# Motherboard.net
KiCad netlist of a schematic drawn in EAGLE
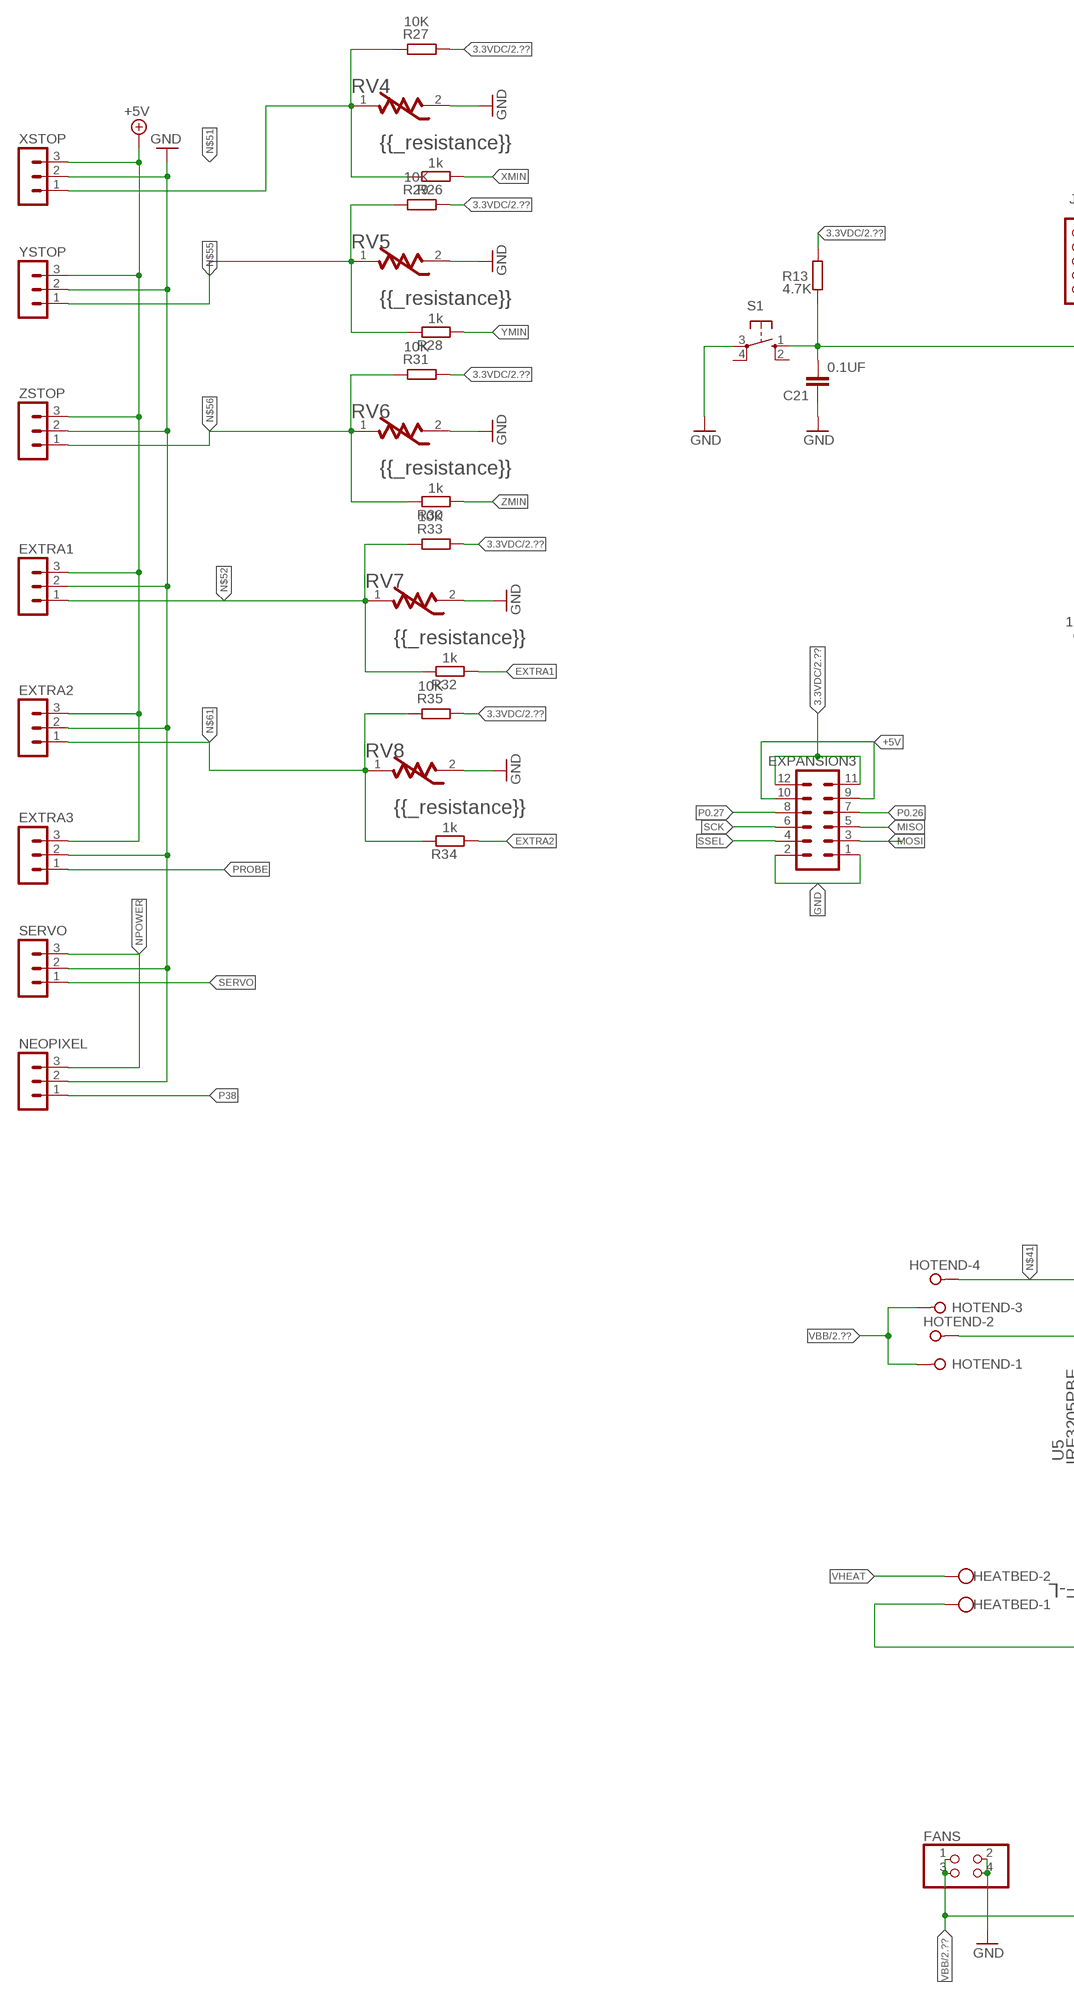
[diagram p0: schematic, sheet 1, part 1 of 2]
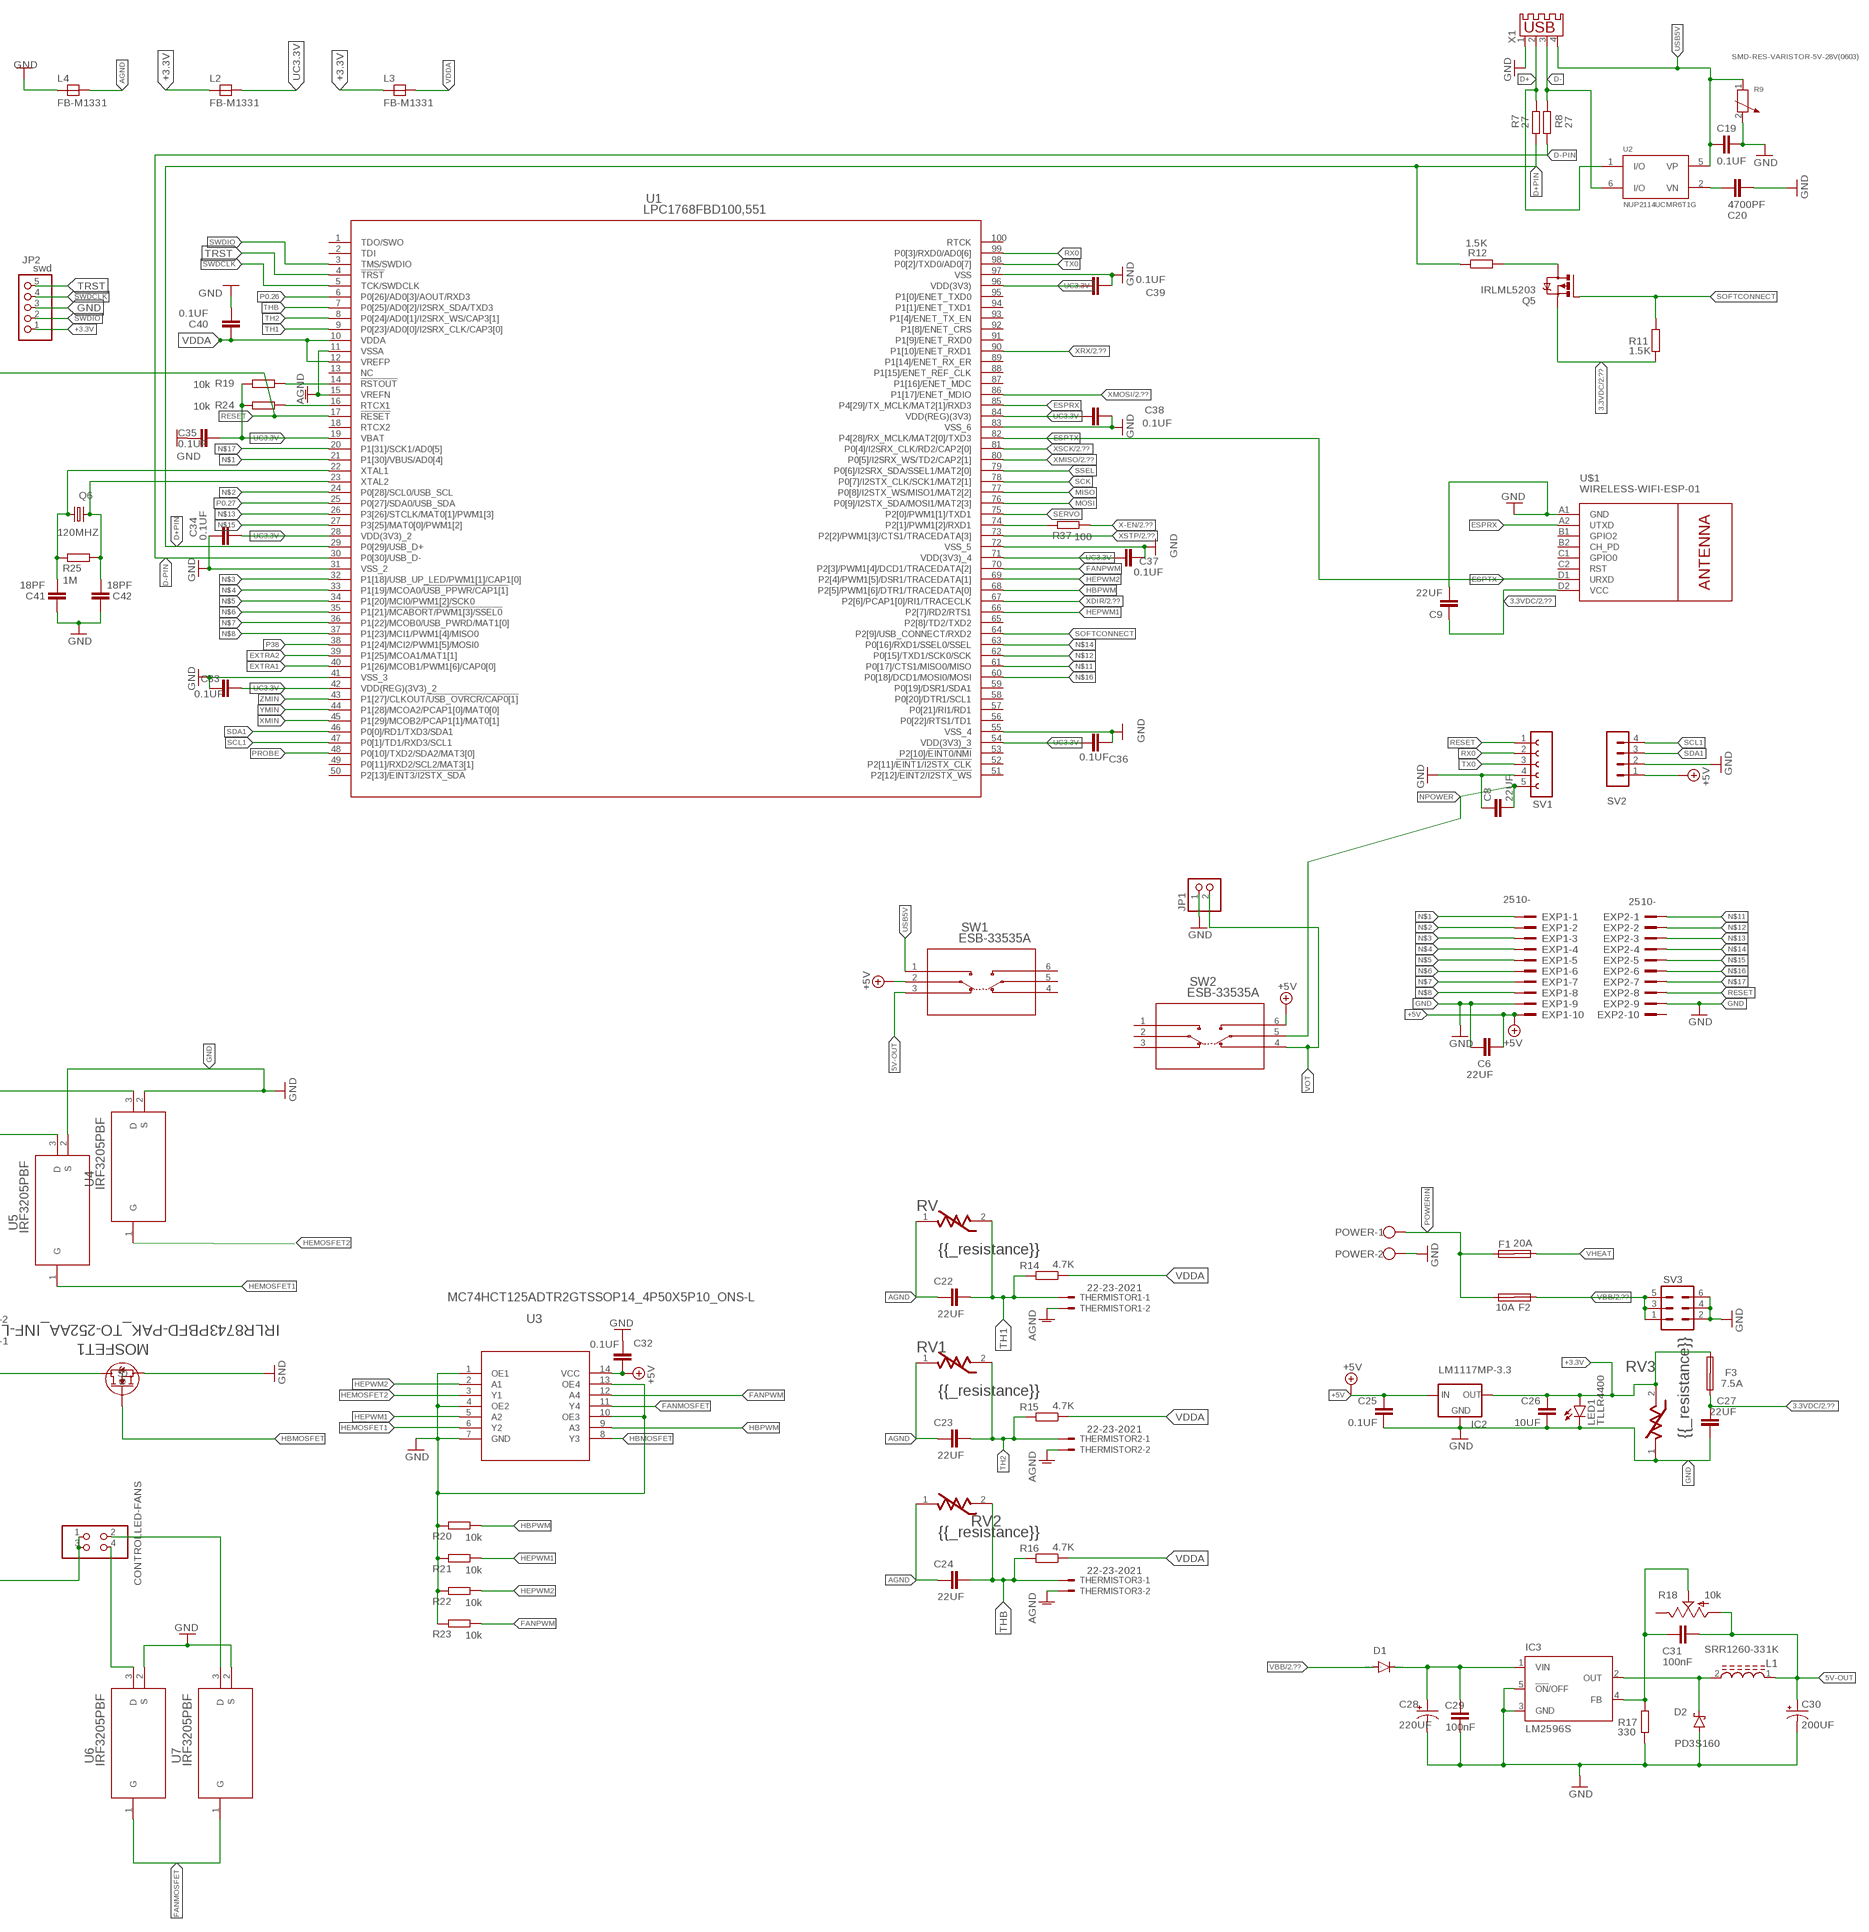
[diagram p1: schematic, sheet 1, part 2 of 2]
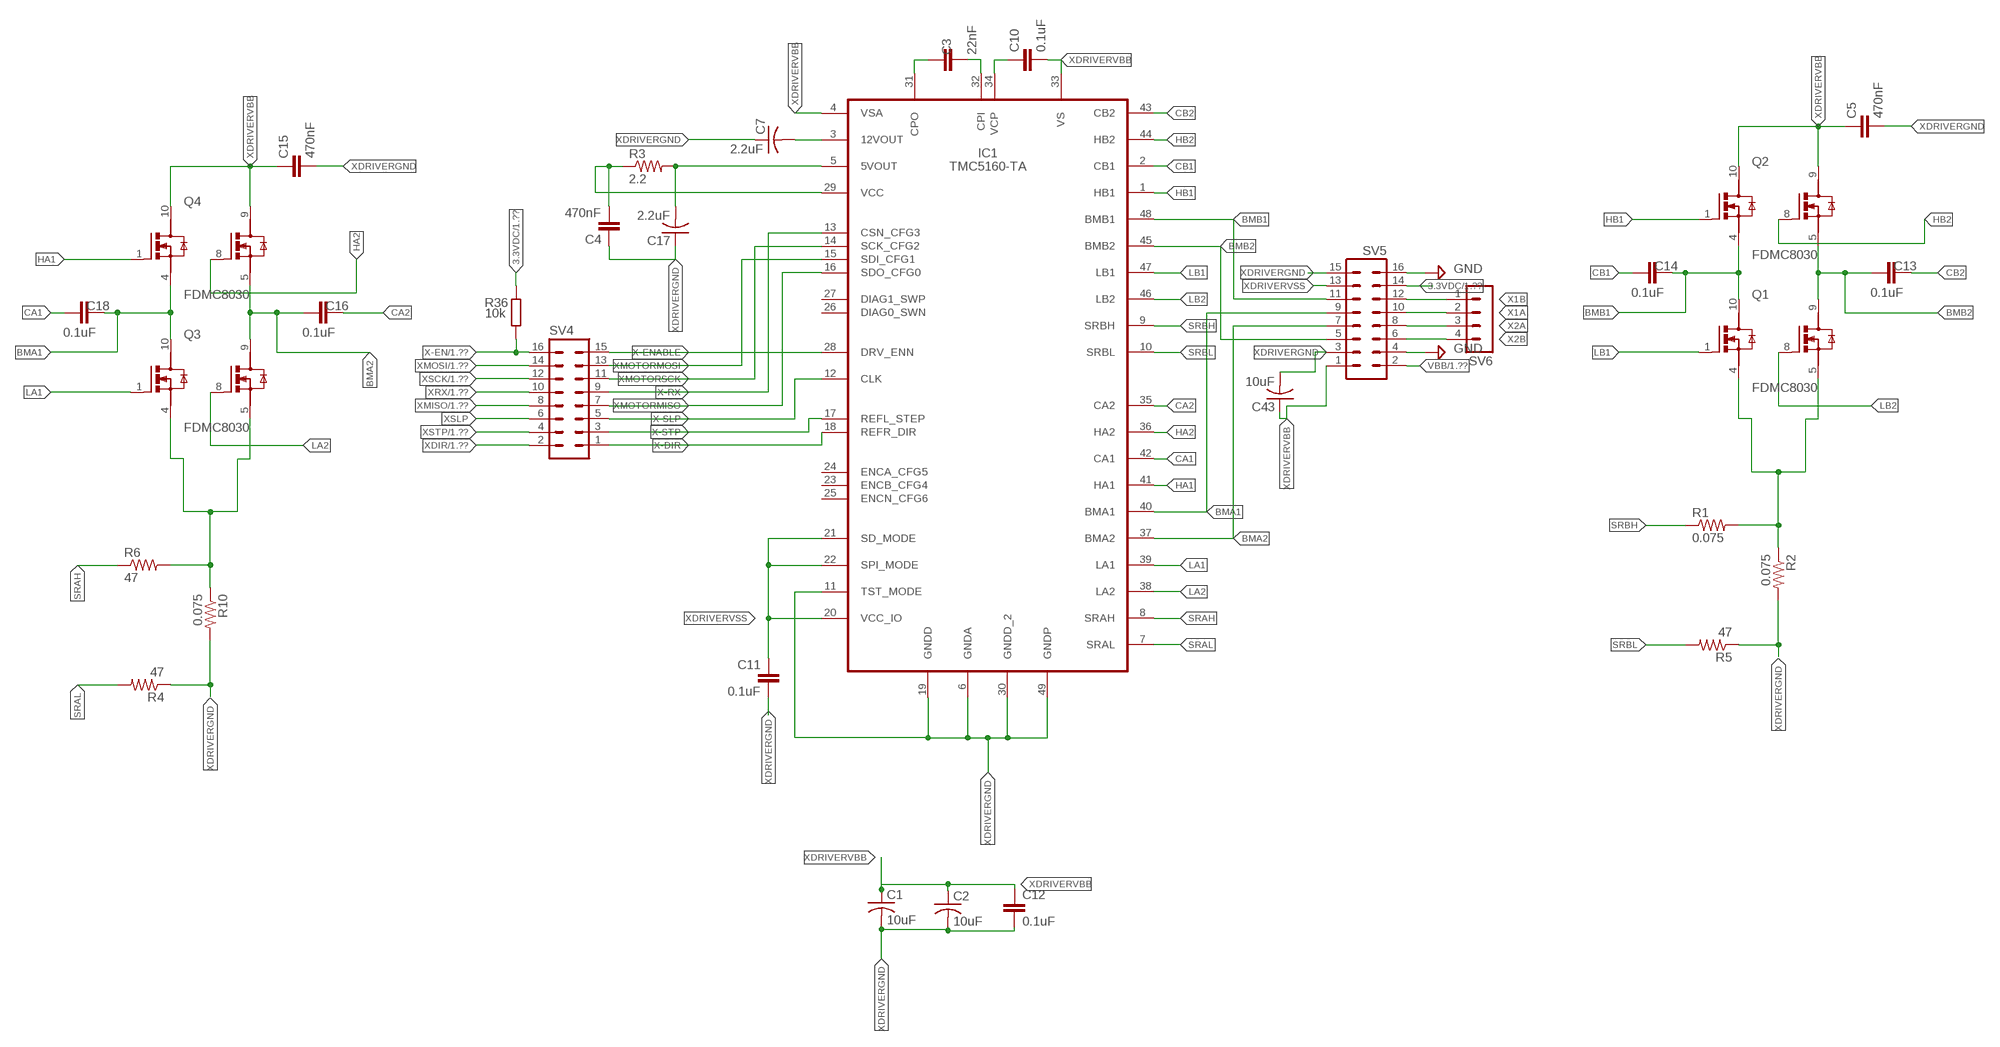
[diagram p2: schematic, sheet 2]

(export (version "E")
  (design (tool "Eeschema 10.0.6"))
  (components
    (comp (ref "C1")
      (value "10uF")
      (footprint "eagle-import:C0805")
      (libsource (lib "eagle-import") (part "C-USC0805"))
    )
    (comp (ref "C2")
      (value "10uF")
      (footprint "eagle-import:C0805")
      (libsource (lib "eagle-import") (part "C-USC0805"))
    )
    (comp (ref "C3")
      (value "22nF")
      (footprint "eagle-import:0603")
      (libsource (lib "eagle-import") (part "22NF/22,000PF-0603-50V-10%"))
    )
    (comp (ref "C4")
      (value "470nF")
      (footprint "eagle-import:0402")
      (libsource (lib "eagle-import") (part "470NF-0402-16V-10%"))
    )
    (comp (ref "C5")
      (value "470nF")
      (footprint "eagle-import:0402")
      (libsource (lib "eagle-import") (part "470NF-0402-16V-10%"))
    )
    (comp (ref "C7")
      (value "2.2uF")
      (footprint "eagle-import:C0402")
      (libsource (lib "eagle-import") (part "C-USC0402"))
    )
    (comp (ref "C10")
      (value "0.1uF")
      (footprint "eagle-import:0402")
      (libsource (lib "eagle-import") (part "0.1UF-0402-16V-10%"))
    )
    (comp (ref "C11")
      (value "0.1uF")
      (footprint "eagle-import:0402")
      (libsource (lib "eagle-import") (part "0.1UF-0402-16V-10%"))
    )
    (comp (ref "C12")
      (value "0.1uF")
      (footprint "eagle-import:0402")
      (libsource (lib "eagle-import") (part "0.1UF-0402-16V-10%"))
    )
    (comp (ref "C13")
      (value "0.1uF")
      (footprint "eagle-import:0402")
      (libsource (lib "eagle-import") (part "0.1UF-0402-16V-10%"))
    )
    (comp (ref "C14")
      (value "0.1uF")
      (footprint "eagle-import:0402")
      (libsource (lib "eagle-import") (part "0.1UF-0402-16V-10%"))
    )
    (comp (ref "C15")
      (value "470nF")
      (footprint "eagle-import:0402")
      (libsource (lib "eagle-import") (part "470NF-0402-16V-10%"))
    )
    (comp (ref "C16")
      (value "0.1uF")
      (footprint "eagle-import:0402")
      (libsource (lib "eagle-import") (part "0.1UF-0402-16V-10%"))
    )
    (comp (ref "C17")
      (value "2.2uF")
      (footprint "eagle-import:C0402")
      (libsource (lib "eagle-import") (part "C-USC0402"))
    )
    (comp (ref "C18")
      (value "0.1uF")
      (footprint "eagle-import:0402")
      (libsource (lib "eagle-import") (part "0.1UF-0402-16V-10%"))
    )
    (comp (ref "C43")
      (value "10uF")
      (footprint "eagle-import:C0805")
      (libsource (lib "eagle-import") (part "C-USC0805"))
    )
    (comp (ref "IC1")
      (value "TMC5160-TA")
      (footprint "eagle-import:TQFP48-EP")
      (fields (field (name "MF") "Trinamic Motion"))
      (libsource (lib "eagle-import") (part "TMC5160-TA"))
    )
    (comp (ref "Q1")
      (value "FDMC8030")
      (footprint "eagle-import:TRANS_FDMC8030")
      (fields (field (name "MF") "ON Semiconductor"))
      (libsource (lib "eagle-import") (part "FDMC8030"))
    )
    (comp (ref "Q2")
      (value "FDMC8030")
      (footprint "eagle-import:TRANS_FDMC8030")
      (fields (field (name "MF") "ON Semiconductor"))
      (libsource (lib "eagle-import") (part "FDMC8030"))
    )
    (comp (ref "Q3")
      (value "FDMC8030")
      (footprint "eagle-import:TRANS_FDMC8030")
      (fields (field (name "MF") "ON Semiconductor"))
      (libsource (lib "eagle-import") (part "FDMC8030"))
    )
    (comp (ref "Q4")
      (value "FDMC8030")
      (footprint "eagle-import:TRANS_FDMC8030")
      (fields (field (name "MF") "ON Semiconductor"))
      (libsource (lib "eagle-import") (part "FDMC8030"))
    )
    (comp (ref "R1")
      (value "0.075")
      (footprint "eagle-import:R1206")
      (libsource (lib "eagle-import") (part "R-US_R1206"))
    )
    (comp (ref "R2")
      (value "0.075")
      (footprint "eagle-import:R1206")
      (libsource (lib "eagle-import") (part "R-US_R1206"))
    )
    (comp (ref "R3")
      (value "2.2")
      (footprint "eagle-import:R0402")
      (libsource (lib "eagle-import") (part "R-US_R0402"))
    )
    (comp (ref "R4")
      (value "47")
      (footprint "eagle-import:R0402")
      (libsource (lib "eagle-import") (part "R-US_R0402"))
    )
    (comp (ref "R5")
      (value "47")
      (footprint "eagle-import:R0402")
      (libsource (lib "eagle-import") (part "R-US_R0402"))
    )
    (comp (ref "R6")
      (value "47")
      (footprint "eagle-import:R0402")
      (libsource (lib "eagle-import") (part "R-US_R0402"))
    )
    (comp (ref "R10")
      (value "0.075")
      (footprint "eagle-import:R1206")
      (libsource (lib "eagle-import") (part "R-US_R1206"))
    )
    (comp (ref "R36")
      (value "10k")
      (footprint "eagle-import:R0805")
      (libsource (lib "eagle-import") (part "R-EU_R0805"))
    )
    (comp (ref "SV4")
      (value "MA08-2")
      (footprint "eagle-import:MA08-2")
      (libsource (lib "eagle-import") (part "MA08-2"))
    )
    (comp (ref "SV5")
      (value "MA08-2")
      (footprint "eagle-import:MA08-2")
      (libsource (lib "eagle-import") (part "MA08-2"))
    )
    (comp (ref "SV6")
      (value "MA04-1")
      (footprint "eagle-import:MA04-1")
      (libsource (lib "eagle-import") (part "MA04-1"))
    )
    (comp (ref "C6")
      (value "22UF")
      (footprint "eagle-import:C0805")
      (libsource (lib "eagle-import") (part "C-EUC0805"))
    )
    (comp (ref "C8")
      (value "22UF")
      (footprint "eagle-import:C0805")
      (libsource (lib "eagle-import") (part "C-EUC0805"))
    )
    (comp (ref "C9")
      (value "22UF")
      (footprint "eagle-import:C0805")
      (libsource (lib "eagle-import") (part "C-EUC0805"))
    )
    (comp (ref "C19")
      (value "0.1UF")
      (footprint "eagle-import:C0805")
      (libsource (lib "eagle-import") (part "C-EUC0805"))
    )
    (comp (ref "C20")
      (value "4700PF")
      (footprint "eagle-import:C0805")
      (libsource (lib "eagle-import") (part "C-EUC0805"))
    )
    (comp (ref "C21")
      (value "0.1UF")
      (footprint "eagle-import:C0805")
      (libsource (lib "eagle-import") (part "C-EUC0805"))
    )
    (comp (ref "C22")
      (value "22UF")
      (footprint "eagle-import:C0805")
      (libsource (lib "eagle-import") (part "C-EUC0805"))
    )
    (comp (ref "C23")
      (value "22UF")
      (footprint "eagle-import:C0805")
      (libsource (lib "eagle-import") (part "C-EUC0805"))
    )
    (comp (ref "C24")
      (value "22UF")
      (footprint "eagle-import:C0805")
      (libsource (lib "eagle-import") (part "C-EUC0805"))
    )
    (comp (ref "C25")
      (value "0.1UF")
      (footprint "eagle-import:C0805")
      (libsource (lib "eagle-import") (part "C-EUC0805"))
    )
    (comp (ref "C26")
      (value "10UF")
      (footprint "eagle-import:C0805")
      (libsource (lib "eagle-import") (part "C-EUC0805"))
    )
    (comp (ref "C27")
      (value "22UF")
      (footprint "eagle-import:C0805")
      (libsource (lib "eagle-import") (part "C-EUC0805"))
    )
    (comp (ref "C28")
      (value "220UF")
      (footprint "eagle-import:E5-10,5")
      (libsource (lib "eagle-import") (part "CPOL-USE5-10.5"))
    )
    (comp (ref "C29")
      (value "100nF")
      (footprint "eagle-import:C0805")
      (libsource (lib "eagle-import") (part "C-EUC0805"))
    )
    (comp (ref "C30")
      (value "200UF")
      (footprint "eagle-import:E5-10,5")
      (libsource (lib "eagle-import") (part "CPOL-USE5-10.5"))
    )
    (comp (ref "C31")
      (value "100nF")
      (footprint "eagle-import:C0805")
      (libsource (lib "eagle-import") (part "C-EUC0805"))
    )
    (comp (ref "C32")
      (value "0.1UF")
      (footprint "eagle-import:C0805")
      (libsource (lib "eagle-import") (part "C-EUC0805"))
    )
    (comp (ref "C33")
      (value "0.1UF")
      (footprint "eagle-import:C0805")
      (libsource (lib "eagle-import") (part "C-EUC0805"))
    )
    (comp (ref "C34")
      (value "0.1UF")
      (footprint "eagle-import:C0805")
      (libsource (lib "eagle-import") (part "C-EUC0805"))
    )
    (comp (ref "C35")
      (value "0.1UF")
      (footprint "eagle-import:C0805")
      (libsource (lib "eagle-import") (part "C-EUC0805"))
    )
    (comp (ref "C36")
      (value "0.1UF")
      (footprint "eagle-import:C0805")
      (libsource (lib "eagle-import") (part "C-EUC0805"))
    )
    (comp (ref "C37")
      (value "0.1UF")
      (footprint "eagle-import:C0805")
      (libsource (lib "eagle-import") (part "C-EUC0805"))
    )
    (comp (ref "C38")
      (value "0.1UF")
      (footprint "eagle-import:C0805")
      (libsource (lib "eagle-import") (part "C-EUC0805"))
    )
    (comp (ref "C39")
      (value "0.1UF")
      (footprint "eagle-import:C0805")
      (libsource (lib "eagle-import") (part "C-EUC0805"))
    )
    (comp (ref "C40")
      (value "0.1UF")
      (footprint "eagle-import:C0805")
      (libsource (lib "eagle-import") (part "C-EUC0805"))
    )
    (comp (ref "C41")
      (value "18PF")
      (footprint "eagle-import:C0805")
      (libsource (lib "eagle-import") (part "C-EUC0805"))
    )
    (comp (ref "C42")
      (value "18PF")
      (footprint "eagle-import:C0805")
      (libsource (lib "eagle-import") (part "C-EUC0805"))
    )
    (comp (ref "CONTROLLED-FANS")
      (value "PINHD-2X2")
      (footprint "eagle-import:2X02")
      (libsource (lib "eagle-import") (part "PINHD-2X2"))
    )
    (comp (ref "D1")
      (value "DIODE-DO214AA")
      (footprint "eagle-import:DO214AA")
      (libsource (lib "eagle-import") (part "DIODE-DO214AA"))
    )
    (comp (ref "D2")
      (value "PD3S160")
      (footprint "eagle-import:POWERDI323")
      (libsource (lib "eagle-import") (part "PD3S160"))
    )
    (comp (ref "EXP1")
      (value "2510-")
      (footprint "eagle-import:PAK100_2500-10")
      (fields (field (name "MF") "3M") (field (name "MPN") "2510-6002UB"))
      (libsource (lib "eagle-import") (part "2510-"))
    )
    (comp (ref "EXP2")
      (value "2510-")
      (footprint "eagle-import:PAK100_2500-10")
      (fields (field (name "MF") "3M") (field (name "MPN") "2510-6002UB"))
      (libsource (lib "eagle-import") (part "2510-"))
    )
    (comp (ref "EXPANSION3")
      (value "MA06-2")
      (footprint "eagle-import:MA06-2")
      (libsource (lib "eagle-import") (part "MA06-2"))
    )
    (comp (ref "EXTRA1")
      (value "MA03-1")
      (footprint "eagle-import:MA03-1")
      (libsource (lib "eagle-import") (part "MA03-1"))
    )
    (comp (ref "EXTRA2")
      (value "MA03-1")
      (footprint "eagle-import:MA03-1")
      (libsource (lib "eagle-import") (part "MA03-1"))
    )
    (comp (ref "EXTRA3")
      (value "MA03-1")
      (footprint "eagle-import:MA03-1")
      (libsource (lib "eagle-import") (part "MA03-1"))
    )
    (comp (ref "F1")
      (value "20A")
      (footprint "eagle-import:SHK20Q")
      (libsource (lib "eagle-import") (part "SHK20Q"))
    )
    (comp (ref "F2")
      (value "10A")
      (footprint "eagle-import:SHK20Q")
      (libsource (lib "eagle-import") (part "SHK20Q"))
    )
    (comp (ref "F3")
      (value "7.5A")
      (footprint "eagle-import:SHK20Q")
      (libsource (lib "eagle-import") (part "SHK20Q"))
    )
    (comp (ref "FANS")
      (value "PINHD-2X2")
      (footprint "eagle-import:2X02")
      (libsource (lib "eagle-import") (part "PINHD-2X2"))
    )
    (comp (ref "HEATBED")
      (value "W237-102")
      (footprint "eagle-import:W237-102")
      (fields (field (name "MPN") "237-102"))
      (libsource (lib "eagle-import") (part "W237-102"))
    )
    (comp (ref "HOTEND")
      (value "W237-04P")
      (footprint "eagle-import:W237-4P")
      (libsource (lib "eagle-import") (part "W237-04P"))
    )
    (comp (ref "IC2")
      (value "LM1117MP-3.3")
      (footprint "eagle-import:SOT223")
      (fields (field (name "MF") "Texas Instruments"))
      (libsource (lib "eagle-import") (part "LM1117?-MP3.3"))
    )
    (comp (ref "IC3")
      (value "LM2596S")
      (footprint "eagle-import:TO263-5")
      (fields (field (name "MF") "NATIONAL SEMICONDUCTOR") (field (name "MPN") "LM2596S-ADJ/NOPB"))
      (libsource (lib "eagle-import") (part "LM2596S"))
    )
    (comp (ref "JP1")
      (value "PINHD-1X2")
      (footprint "eagle-import:1X02")
      (libsource (lib "eagle-import") (part "PINHD-1X2"))
    )
    (comp (ref "JP2")
      (value "swd")
      (footprint "eagle-import:1X05")
      (libsource (lib "eagle-import") (part "PINHD-1X5"))
    )
    (comp (ref "L1")
      (value "SRR1260-331K")
      (footprint "eagle-import:INDP125125X600N")
      (fields (field (name "MF") "Bourns"))
      (libsource (lib "eagle-import") (part "SRR1260-331K"))
    )
    (comp (ref "L2")
      (value "FB-M1331")
      (footprint "eagle-import:M1331")
      (libsource (lib "eagle-import") (part "FB-M1331"))
    )
    (comp (ref "L3")
      (value "FB-M1331")
      (footprint "eagle-import:M1331")
      (libsource (lib "eagle-import") (part "FB-M1331"))
    )
    (comp (ref "L4")
      (value "FB-M1331")
      (footprint "eagle-import:M1331")
      (libsource (lib "eagle-import") (part "FB-M1331"))
    )
    (comp (ref "LED1")
      (value "TLLR4400")
      (footprint "eagle-import:LED3MM")
      (fields (field (name "MF") "VISHAY SEMICONDUCTOR"))
      (libsource (lib "eagle-import") (part "TLLR4400"))
    )
    (comp (ref "MOSFET1")
      (value "IRLR8743PBFD-PAK_TO-252AA_INF-L")
      (footprint "eagle-import:D-PAK_TO-252AA_INF-L")
      (fields
        (field (name "MANUFACTURER_PART_NUMBER") "IRLR8743PBF")
        (field (name "COPYRIGHT") "Copyright (C) 2018 Accelerated Designs. All rights reserved")
      )
      (libsource (lib "eagle-import") (part "IRLR8743PBFD-PAK_TO-252AA_INF-L"))
    )
    (comp (ref "NEOPIXEL")
      (value "MA03-1")
      (footprint "eagle-import:MA03-1")
      (libsource (lib "eagle-import") (part "MA03-1"))
    )
    (comp (ref "POWER")
      (value "W237-102")
      (footprint "eagle-import:W237-102")
      (fields (field (name "MPN") "237-102"))
      (libsource (lib "eagle-import") (part "W237-102"))
    )
    (comp (ref "Q5")
      (value "IRLML5203")
      (footprint "eagle-import:MICRO3")
      (libsource (lib "eagle-import") (part "IRLML5203"))
    )
    (comp (ref "Q6")
      (value "120MHZ")
      (footprint "eagle-import:HC49_S")
      (libsource (lib "eagle-import") (part "CRYSTALHC49S"))
    )
    (comp (ref "R7")
      (value "27")
      (footprint "eagle-import:R0805")
      (libsource (lib "eagle-import") (part "R-EU_R0805"))
    )
    (comp (ref "R8")
      (value "27")
      (footprint "eagle-import:R0805")
      (libsource (lib "eagle-import") (part "R-EU_R0805"))
    )
    (comp (ref "R9")
      (value "SMD-RES-VARISTOR-5V-28V(0603)")
      (footprint "eagle-import:R0603")
      (fields
        (field (name "DIGI-KEY_PART_NUMBER") "CG0603MLC-05ECT-ND")
        (field (name "MF") "Bourns")
        (field (name "MP") "CG0603MLC-05E")
      )
      (libsource (lib "eagle-import") (part "SMD-RES-VARISTOR-5V-28V(0603)"))
    )
    (comp (ref "R11")
      (value "1.5K")
      (footprint "eagle-import:R0805")
      (libsource (lib "eagle-import") (part "R-EU_R0805"))
    )
    (comp (ref "R12")
      (value "1.5K")
      (footprint "eagle-import:R0805")
      (libsource (lib "eagle-import") (part "R-EU_R0805"))
    )
    (comp (ref "R13")
      (value "4.7K")
      (footprint "eagle-import:R0805")
      (libsource (lib "eagle-import") (part "R-EU_R0805"))
    )
    (comp (ref "R14")
      (value "4.7K")
      (footprint "eagle-import:R0805")
      (libsource (lib "eagle-import") (part "R-EU_R0805"))
    )
    (comp (ref "R15")
      (value "4.7K")
      (footprint "eagle-import:R0805")
      (libsource (lib "eagle-import") (part "R-EU_R0805"))
    )
    (comp (ref "R16")
      (value "4.7K")
      (footprint "eagle-import:R0805")
      (libsource (lib "eagle-import") (part "R-EU_R0805"))
    )
    (comp (ref "R17")
      (value "330")
      (footprint "eagle-import:R0805")
      (libsource (lib "eagle-import") (part "R-EU_R0805"))
    )
    (comp (ref "R18")
      (value "10k")
      (footprint "eagle-import:B64Y")
      (libsource (lib "eagle-import") (part "TRIM_US-B64Y"))
    )
    (comp (ref "R19")
      (value "10k")
      (footprint "eagle-import:R0805")
      (libsource (lib "eagle-import") (part "R-EU_R0805"))
    )
    (comp (ref "R20")
      (value "10k")
      (footprint "eagle-import:R0805")
      (libsource (lib "eagle-import") (part "R-EU_R0805"))
    )
    (comp (ref "R21")
      (value "10k")
      (footprint "eagle-import:R0805")
      (libsource (lib "eagle-import") (part "R-EU_R0805"))
    )
    (comp (ref "R22")
      (value "10k")
      (footprint "eagle-import:R0805")
      (libsource (lib "eagle-import") (part "R-EU_R0805"))
    )
    (comp (ref "R23")
      (value "10k")
      (footprint "eagle-import:R0805")
      (libsource (lib "eagle-import") (part "R-EU_R0805"))
    )
    (comp (ref "R24")
      (value "10k")
      (footprint "eagle-import:R0805")
      (libsource (lib "eagle-import") (part "R-EU_R0805"))
    )
    (comp (ref "R25")
      (value "1M")
      (footprint "eagle-import:R0805")
      (libsource (lib "eagle-import") (part "R-EU_R0805"))
    )
    (comp (ref "R26")
      (value "1k")
      (footprint "eagle-import:R0805")
      (libsource (lib "eagle-import") (part "R-EU_R0805"))
    )
    (comp (ref "R27")
      (value "10K")
      (footprint "eagle-import:R0805")
      (libsource (lib "eagle-import") (part "R-EU_R0805"))
    )
    (comp (ref "R28")
      (value "1k")
      (footprint "eagle-import:R0805")
      (libsource (lib "eagle-import") (part "R-EU_R0805"))
    )
    (comp (ref "R29")
      (value "10K")
      (footprint "eagle-import:R0805")
      (libsource (lib "eagle-import") (part "R-EU_R0805"))
    )
    (comp (ref "R30")
      (value "1k")
      (footprint "eagle-import:R0805")
      (libsource (lib "eagle-import") (part "R-EU_R0805"))
    )
    (comp (ref "R31")
      (value "10K")
      (footprint "eagle-import:R0805")
      (libsource (lib "eagle-import") (part "R-EU_R0805"))
    )
    (comp (ref "R32")
      (value "1k")
      (footprint "eagle-import:R0805")
      (libsource (lib "eagle-import") (part "R-EU_R0805"))
    )
    (comp (ref "R33")
      (value "10K")
      (footprint "eagle-import:R0805")
      (libsource (lib "eagle-import") (part "R-EU_R0805"))
    )
    (comp (ref "R34")
      (value "1k")
      (footprint "eagle-import:R0805")
      (libsource (lib "eagle-import") (part "R-EU_R0805"))
    )
    (comp (ref "R35")
      (value "10K")
      (footprint "eagle-import:R0805")
      (libsource (lib "eagle-import") (part "R-EU_R0805"))
    )
    (comp (ref "R37")
      (value "100")
      (footprint "eagle-import:R0805")
      (libsource (lib "eagle-import") (part "R-EU_R0805"))
    )
    (comp (ref "RV")
      (value "BOURNS_INC._CG0603MLC-3.3LEBOURNS_INC._CG0603MLC-3.3LE_0_1")
      (footprint "eagle-import:BOURNS_INC._CG0603MLC-3.3LE_1")
      (fields
        (field (name "DIGIKEY_PART_NUMBER") "CG0603MLC-3.3LECT-ND")
        (field (name "MF") "Bourns Inc.")
        (field (name "MOUSER_PART_NUMBER") "652-CG0603MLC-3.3LE")
      )
      (libsource (lib "eagle-import") (part "BOURNS_INC._CG0603MLC-3.3LEBOURNS_INC._CG0603MLC-3.3LE_0_1"))
    )
    (comp (ref "RV1")
      (value "BOURNS_INC._CG0603MLC-3.3LEBOURNS_INC._CG0603MLC-3.3LE_0_1")
      (footprint "eagle-import:BOURNS_INC._CG0603MLC-3.3LE_1")
      (fields
        (field (name "DIGIKEY_PART_NUMBER") "CG0603MLC-3.3LECT-ND")
        (field (name "MF") "Bourns Inc.")
        (field (name "MOUSER_PART_NUMBER") "652-CG0603MLC-3.3LE")
      )
      (libsource (lib "eagle-import") (part "BOURNS_INC._CG0603MLC-3.3LEBOURNS_INC._CG0603MLC-3.3LE_0_1"))
    )
    (comp (ref "RV2")
      (value "BOURNS_INC._CG0603MLC-3.3LEBOURNS_INC._CG0603MLC-3.3LE_0_1")
      (footprint "eagle-import:BOURNS_INC._CG0603MLC-3.3LE_1")
      (fields
        (field (name "DIGIKEY_PART_NUMBER") "CG0603MLC-3.3LECT-ND")
        (field (name "MF") "Bourns Inc.")
        (field (name "MOUSER_PART_NUMBER") "652-CG0603MLC-3.3LE")
      )
      (libsource (lib "eagle-import") (part "BOURNS_INC._CG0603MLC-3.3LEBOURNS_INC._CG0603MLC-3.3LE_0_1"))
    )
    (comp (ref "RV3")
      (value "BOURNS_INC._CG0603MLC-3.3LEBOURNS_INC._CG0603MLC-3.3LE_0_1")
      (footprint "eagle-import:BOURNS_INC._CG0603MLC-3.3LE_1")
      (fields
        (field (name "DIGIKEY_PART_NUMBER") "CG0603MLC-3.3LECT-ND")
        (field (name "MF") "Bourns Inc.")
        (field (name "MOUSER_PART_NUMBER") "652-CG0603MLC-3.3LE")
      )
      (libsource (lib "eagle-import") (part "BOURNS_INC._CG0603MLC-3.3LEBOURNS_INC._CG0603MLC-3.3LE_0_1"))
    )
    (comp (ref "RV4")
      (value "BOURNS_INC._CG0603MLC-3.3LEBOURNS_INC._CG0603MLC-3.3LE_0_1")
      (footprint "eagle-import:BOURNS_INC._CG0603MLC-3.3LE_1")
      (fields
        (field (name "DIGIKEY_PART_NUMBER") "CG0603MLC-3.3LECT-ND")
        (field (name "MF") "Bourns Inc.")
        (field (name "MOUSER_PART_NUMBER") "652-CG0603MLC-3.3LE")
      )
      (libsource (lib "eagle-import") (part "BOURNS_INC._CG0603MLC-3.3LEBOURNS_INC._CG0603MLC-3.3LE_0_1"))
    )
    (comp (ref "RV5")
      (value "BOURNS_INC._CG0603MLC-3.3LEBOURNS_INC._CG0603MLC-3.3LE_0_1")
      (footprint "eagle-import:BOURNS_INC._CG0603MLC-3.3LE_1")
      (fields
        (field (name "DIGIKEY_PART_NUMBER") "CG0603MLC-3.3LECT-ND")
        (field (name "MF") "Bourns Inc.")
        (field (name "MOUSER_PART_NUMBER") "652-CG0603MLC-3.3LE")
      )
      (libsource (lib "eagle-import") (part "BOURNS_INC._CG0603MLC-3.3LEBOURNS_INC._CG0603MLC-3.3LE_0_1"))
    )
    (comp (ref "RV6")
      (value "BOURNS_INC._CG0603MLC-3.3LEBOURNS_INC._CG0603MLC-3.3LE_0_1")
      (footprint "eagle-import:BOURNS_INC._CG0603MLC-3.3LE_1")
      (fields
        (field (name "DIGIKEY_PART_NUMBER") "CG0603MLC-3.3LECT-ND")
        (field (name "MF") "Bourns Inc.")
        (field (name "MOUSER_PART_NUMBER") "652-CG0603MLC-3.3LE")
      )
      (libsource (lib "eagle-import") (part "BOURNS_INC._CG0603MLC-3.3LEBOURNS_INC._CG0603MLC-3.3LE_0_1"))
    )
    (comp (ref "RV7")
      (value "BOURNS_INC._CG0603MLC-3.3LEBOURNS_INC._CG0603MLC-3.3LE_0_1")
      (footprint "eagle-import:BOURNS_INC._CG0603MLC-3.3LE_1")
      (fields
        (field (name "DIGIKEY_PART_NUMBER") "CG0603MLC-3.3LECT-ND")
        (field (name "MF") "Bourns Inc.")
        (field (name "MOUSER_PART_NUMBER") "652-CG0603MLC-3.3LE")
      )
      (libsource (lib "eagle-import") (part "BOURNS_INC._CG0603MLC-3.3LEBOURNS_INC._CG0603MLC-3.3LE_0_1"))
    )
    (comp (ref "RV8")
      (value "BOURNS_INC._CG0603MLC-3.3LEBOURNS_INC._CG0603MLC-3.3LE_0_1")
      (footprint "eagle-import:BOURNS_INC._CG0603MLC-3.3LE_1")
      (fields
        (field (name "DIGIKEY_PART_NUMBER") "CG0603MLC-3.3LECT-ND")
        (field (name "MF") "Bourns Inc.")
        (field (name "MOUSER_PART_NUMBER") "652-CG0603MLC-3.3LE")
      )
      (libsource (lib "eagle-import") (part "BOURNS_INC._CG0603MLC-3.3LEBOURNS_INC._CG0603MLC-3.3LE_0_1"))
    )
    (comp (ref "S1")
      (value "10-XX")
      (footprint "eagle-import:B3F-10XX")
      (fields (field (name "MPN") "B3F-1000"))
      (libsource (lib "eagle-import") (part "10-XX"))
    )
    (comp (ref "SERVO")
      (value "MA03-1")
      (footprint "eagle-import:MA03-1")
      (libsource (lib "eagle-import") (part "MA03-1"))
    )
    (comp (ref "SV1")
      (value "FE05-1")
      (footprint "eagle-import:FE05-1")
      (libsource (lib "eagle-import") (part "FE05-1"))
    )
    (comp (ref "SV2")
      (value "MA04-1")
      (footprint "eagle-import:MA04-1")
      (libsource (lib "eagle-import") (part "MA04-1"))
    )
    (comp (ref "SV3")
      (value "MA03-2")
      (footprint "eagle-import:MA03-2")
      (libsource (lib "eagle-import") (part "MA03-2"))
    )
    (comp (ref "SW1")
      (value "ESB-33535A")
      (footprint "eagle-import:ESB335_PAN")
      (fields (field (name "COPYRIGHT") "Copyright (C) 2018 Accelerated Designs. All rights reserved"))
      (libsource (lib "eagle-import") (part "ESB-33535A"))
    )
    (comp (ref "SW2")
      (value "ESB-33535A")
      (footprint "eagle-import:ESB335_PAN")
      (fields (field (name "COPYRIGHT") "Copyright (C) 2018 Accelerated Designs. All rights reserved"))
      (libsource (lib "eagle-import") (part "ESB-33535A"))
    )
    (comp (ref "THERMISTOR1")
      (value "22-23-2021")
      (footprint "eagle-import:22-23-2021")
      (fields (field (name "MF") "MOLEX"))
      (libsource (lib "eagle-import") (part "22-23-2021"))
    )
    (comp (ref "THERMISTOR2")
      (value "22-23-2021")
      (footprint "eagle-import:22-23-2021")
      (fields (field (name "MF") "MOLEX"))
      (libsource (lib "eagle-import") (part "22-23-2021"))
    )
    (comp (ref "THERMISTOR3")
      (value "22-23-2021")
      (footprint "eagle-import:22-23-2021")
      (fields (field (name "MF") "MOLEX"))
      (libsource (lib "eagle-import") (part "22-23-2021"))
    )
    (comp (ref "U$1")
      (value "WIRELESS-WIFI-ESP-01")
      (footprint "eagle-import:WIRELESS-WIFI-ESP-01")
      (libsource (lib "eagle-import") (part "WIRELESS-WIFI-ESP-01"))
    )
    (comp (ref "U1")
      (value "LPC1768FBD100,551")
      (footprint "eagle-import:LQFP100_14X14_NXP")
      (fields (field (name "COPYRIGHT") "Copyright (C) 2016 Accelerated Designs. All rights reserved"))
      (libsource (lib "eagle-import") (part "LPC1768FBD100,551"))
    )
    (comp (ref "U2")
      (value "NUP2114UCMR6T1G")
      (footprint "eagle-import:SOP95P275X110-6N")
      (fields
        (field (name "DIGI-KEY_PART_NUMBER") "NUP2114UCMR6T1GOSCT-ND")
        (field (name "MF") "ON Semiconductor")
      )
      (libsource (lib "eagle-import") (part "NUP2114UCMR6T1G"))
    )
    (comp (ref "U3")
      (value "MC74HCT125ADTR2GTSSOP14_4P50X5P10_ONS-L")
      (footprint "eagle-import:TSSOP14_4P50X5P10_ONS-L")
      (fields
        (field (name "MANUFACTURER_PART_NUMBER") "MC74HCT125ADTR2G")
        (field (name "COPYRIGHT") "Copyright (C) 2016 Accelerated Designs. All rights reserved")
      )
      (libsource (lib "eagle-import") (part "MC74HCT125ADTR2GTSSOP14_4P50X5P10_ONS-L"))
    )
    (comp (ref "U4")
      (value "IRF3205PBF")
      (footprint "eagle-import:PG-TO220-3_INF")
      (fields (field (name "COPYRIGHT") "Copyright (C) 2018 Accelerated Designs. All rights reserved"))
      (libsource (lib "eagle-import") (part "IRF3205PBF"))
    )
    (comp (ref "U5")
      (value "IRF3205PBF")
      (footprint "eagle-import:PG-TO220-3_INF")
      (fields (field (name "COPYRIGHT") "Copyright (C) 2018 Accelerated Designs. All rights reserved"))
      (libsource (lib "eagle-import") (part "IRF3205PBF"))
    )
    (comp (ref "U6")
      (value "IRF3205PBF")
      (footprint "eagle-import:PG-TO220-3_INF")
      (fields (field (name "COPYRIGHT") "Copyright (C) 2018 Accelerated Designs. All rights reserved"))
      (libsource (lib "eagle-import") (part "IRF3205PBF"))
    )
    (comp (ref "U7")
      (value "IRF3205PBF")
      (footprint "eagle-import:PG-TO220-3_INF")
      (fields (field (name "COPYRIGHT") "Copyright (C) 2018 Accelerated Designs. All rights reserved"))
      (libsource (lib "eagle-import") (part "IRF3205PBF"))
    )
    (comp (ref "X1")
      (value "USB-A003")
      (footprint "eagle-import:USB-A003")
      (libsource (lib "eagle-import") (part "USB-A003"))
    )
    (comp (ref "XSTOP")
      (value "MA03-1")
      (footprint "eagle-import:MA03-1")
      (libsource (lib "eagle-import") (part "MA03-1"))
    )
    (comp (ref "YSTOP")
      (value "MA03-1")
      (footprint "eagle-import:MA03-1")
      (libsource (lib "eagle-import") (part "MA03-1"))
    )
    (comp (ref "ZSTOP")
      (value "MA03-1")
      (footprint "eagle-import:MA03-1")
      (libsource (lib "eagle-import") (part "MA03-1"))
    )
  )
  (nets
    (net (code "1") (name "+3.3V") (class "Default")
      (node (ref "C26") (pin "1") (pinfunction "1_1") (pintype "passive"))
      (node (ref "F3") (pin "2A") (pinfunction "2A_2A") (pintype "passive"))
      (node (ref "IC2") (pin "2") (pinfunction "OUT_2") (pintype "passive"))
      (node (ref "IC2") (pin "4") (pinfunction "OUT_4") (pintype "passive"))
      (node (ref "JP2") (pin "1") (pinfunction "1_1") (pintype "passive"))
      (node (ref "L2") (pin "1") (pinfunction "1_1") (pintype "passive"))
      (node (ref "L3") (pin "1") (pinfunction "1_1") (pintype "passive"))
      (node (ref "LED1") (pin "A") (pinfunction "A_A") (pintype "passive"))
      (node (ref "RV3") (pin "2") (pinfunction "2_2") (pintype "passive"))
    )
    (net (code "2") (name "+5V") (class "Default")
      (node (ref "C25") (pin "1") (pinfunction "1_1") (pintype "passive"))
      (node (ref "C32") (pin "2") (pinfunction "2_2") (pintype "passive"))
      (node (ref "C6") (pin "1") (pinfunction "1_1") (pintype "passive"))
      (node (ref "EXP1") (pin "10") (pinfunction "KL_10") (pintype "passive"))
      (node (ref "EXPANSION3") (pin "10") (pinfunction "10_10") (pintype "passive"))
      (node (ref "EXPANSION3") (pin "9") (pinfunction "9_9") (pintype "passive"))
      (node (ref "EXTRA1") (pin "3") (pinfunction "3_3") (pintype "passive"))
      (node (ref "EXTRA2") (pin "3") (pinfunction "3_3") (pintype "passive"))
      (node (ref "EXTRA3") (pin "3") (pinfunction "3_3") (pintype "passive"))
      (node (ref "IC2") (pin "3") (pinfunction "IN_3") (pintype "input"))
      (node (ref "SV2") (pin "1") (pinfunction "1_1") (pintype "passive"))
      (node (ref "SW1") (pin "2") (pinfunction "2_2") (pintype "passive"))
      (node (ref "SW2") (pin "6") (pinfunction "6_6") (pintype "passive"))
      (node (ref "U3") (pin "14") (pinfunction "VCC_14") (pintype "power_in"))
      (node (ref "XSTOP") (pin "3") (pinfunction "3_3") (pintype "passive"))
      (node (ref "YSTOP") (pin "3") (pinfunction "3_3") (pintype "passive"))
      (node (ref "ZSTOP") (pin "3") (pinfunction "3_3") (pintype "passive"))
    )
    (net (code "3") (name "3.3VDC") (class "Default")
      (node (ref "C27") (pin "1") (pinfunction "1_1") (pintype "passive"))
      (node (ref "C9") (pin "1") (pinfunction "1_1") (pintype "passive"))
      (node (ref "EXPANSION3") (pin "11") (pinfunction "11_11") (pintype "passive"))
      (node (ref "EXPANSION3") (pin "12") (pinfunction "12_12") (pintype "passive"))
      (node (ref "F3") (pin "1A") (pinfunction "1A_1A") (pintype "passive"))
      (node (ref "Q5") (pin "2") (pinfunction "S_2") (pintype "passive"))
      (node (ref "R11") (pin "2") (pinfunction "2_2") (pintype "passive"))
      (node (ref "R13") (pin "1") (pinfunction "1_1") (pintype "passive"))
      (node (ref "R27") (pin "2") (pinfunction "2_2") (pintype "passive"))
      (node (ref "R29") (pin "2") (pinfunction "2_2") (pintype "passive"))
      (node (ref "R31") (pin "2") (pinfunction "2_2") (pintype "passive"))
      (node (ref "R33") (pin "2") (pinfunction "2_2") (pintype "passive"))
      (node (ref "R35") (pin "2") (pinfunction "2_2") (pintype "passive"))
      (node (ref "R36") (pin "1") (pinfunction "1_1") (pintype "passive"))
      (node (ref "SV5") (pin "14") (pinfunction "14_14") (pintype "passive"))
      (node (ref "U$1") (pin "D2") (pinfunction "VCC_D2") (pintype "power_in"))
    )
    (net (code "4") (name "5V-OUT") (class "Default")
      (node (ref "C30") (pin "+") (pinfunction "+_+") (pintype "passive"))
      (node (ref "C31") (pin "2") (pinfunction "2_2") (pintype "passive"))
      (node (ref "L1") (pin "1") (pinfunction "1_1") (pintype "passive"))
      (node (ref "R18") (pin "A") (pinfunction "A_A") (pintype "passive"))
      (node (ref "SW1") (pin "3") (pinfunction "3_3") (pintype "passive"))
    )
    (net (code "5") (name "AGND") (class "Default")
      (node (ref "C22") (pin "1") (pinfunction "1_1") (pintype "passive"))
      (node (ref "C23") (pin "1") (pinfunction "1_1") (pintype "passive"))
      (node (ref "C24") (pin "1") (pinfunction "1_1") (pintype "passive"))
      (node (ref "L4") (pin "2") (pinfunction "2_2") (pintype "passive"))
      (node (ref "RV") (pin "1") (pinfunction "1_1") (pintype "passive"))
      (node (ref "RV1") (pin "1") (pinfunction "1_1") (pintype "passive"))
      (node (ref "RV2") (pin "1") (pinfunction "1_1") (pintype "passive"))
      (node (ref "THERMISTOR1") (pin "2") (pinfunction "S_2") (pintype "passive"))
      (node (ref "THERMISTOR2") (pin "2") (pinfunction "S_2") (pintype "passive"))
      (node (ref "THERMISTOR3") (pin "2") (pinfunction "S_2") (pintype "passive"))
      (node (ref "U1") (pin "11") (pinfunction "VSSA_11") (pintype "power_in"))
      (node (ref "U1") (pin "15") (pinfunction "VREFN_15") (pintype "input"))
    )
    (net (code "6") (name "BMA1") (class "Default")
      (node (ref "C18") (pin "2") (pinfunction "2_2") (pintype "passive"))
      (node (ref "IC1") (pin "40") (pinfunction "BMA1_40") (pintype "input"))
      (node (ref "Q3") (pin "10") (pinfunction "D1_10") (pintype "passive"))
      (node (ref "Q4") (pin "4") (pinfunction "S1_4") (pintype "passive"))
      (node (ref "SV5") (pin "9") (pinfunction "9_9") (pintype "passive"))
    )
    (net (code "7") (name "BMA2") (class "Default")
      (node (ref "C16") (pin "1") (pinfunction "1_1") (pintype "passive"))
      (node (ref "IC1") (pin "37") (pinfunction "BMA2_37") (pintype "input"))
      (node (ref "Q3") (pin "9") (pinfunction "D2_9") (pintype "passive"))
      (node (ref "Q4") (pin "5") (pinfunction "S2_5") (pintype "passive"))
      (node (ref "SV5") (pin "7") (pinfunction "7_7") (pintype "passive"))
    )
    (net (code "8") (name "BMB1") (class "Default")
      (node (ref "C14") (pin "2") (pinfunction "2_2") (pintype "passive"))
      (node (ref "IC1") (pin "48") (pinfunction "BMB1_48") (pintype "input"))
      (node (ref "Q1") (pin "10") (pinfunction "D1_10") (pintype "passive"))
      (node (ref "Q2") (pin "4") (pinfunction "S1_4") (pintype "passive"))
      (node (ref "SV5") (pin "11") (pinfunction "11_11") (pintype "passive"))
    )
    (net (code "9") (name "BMB2") (class "Default")
      (node (ref "C13") (pin "1") (pinfunction "1_1") (pintype "passive"))
      (node (ref "IC1") (pin "45") (pinfunction "BMB2_45") (pintype "input"))
      (node (ref "Q1") (pin "9") (pinfunction "D2_9") (pintype "passive"))
      (node (ref "Q2") (pin "5") (pinfunction "S2_5") (pintype "passive"))
      (node (ref "SV5") (pin "5") (pinfunction "5_5") (pintype "passive"))
    )
    (net (code "10") (name "CA1") (class "Default")
      (node (ref "C18") (pin "1") (pinfunction "1_1") (pintype "passive"))
      (node (ref "IC1") (pin "42") (pinfunction "CA1_42") (pintype "input"))
    )
    (net (code "11") (name "CA2") (class "Default")
      (node (ref "C16") (pin "2") (pinfunction "2_2") (pintype "passive"))
      (node (ref "IC1") (pin "35") (pinfunction "CA2_35") (pintype "input"))
    )
    (net (code "12") (name "CB1") (class "Default")
      (node (ref "C14") (pin "1") (pinfunction "1_1") (pintype "passive"))
      (node (ref "IC1") (pin "2") (pinfunction "CB1_2") (pintype "input"))
    )
    (net (code "13") (name "CB2") (class "Default")
      (node (ref "C13") (pin "2") (pinfunction "2_2") (pintype "passive"))
      (node (ref "IC1") (pin "43") (pinfunction "CB2_43") (pintype "input"))
    )
    (net (code "14") (name "D+") (class "Default")
      (node (ref "R7") (pin "2") (pinfunction "2_2") (pintype "passive"))
      (node (ref "U2") (pin "1") (pinfunction "I/O_1") (pintype "bidirectional"))
      (node (ref "X1") (pin "2") (pinfunction "2_2") (pintype "passive"))
    )
    (net (code "15") (name "D+PIN") (class "Default")
      (node (ref "R12") (pin "1") (pinfunction "1_1") (pintype "passive"))
      (node (ref "R7") (pin "1") (pinfunction "1_1") (pintype "passive"))
      (node (ref "U1") (pin "29") (pinfunction "P0[29]/USB_D+_29") (pintype "bidirectional"))
    )
    (net (code "16") (name "D-") (class "Default")
      (node (ref "R8") (pin "2") (pinfunction "2_2") (pintype "passive"))
      (node (ref "U2") (pin "6") (pinfunction "I/O_6") (pintype "bidirectional"))
      (node (ref "X1") (pin "3") (pinfunction "3_3") (pintype "passive"))
    )
    (net (code "17") (name "D-PIN") (class "Default")
      (node (ref "R8") (pin "1") (pinfunction "1_1") (pintype "passive"))
      (node (ref "U1") (pin "30") (pinfunction "P0[30]/USB_D-_30") (pintype "bidirectional"))
    )
    (net (code "18") (name "ESPRX") (class "Default")
      (node (ref "U$1") (pin "A2") (pinfunction "UTXD_A2") (pintype "bidirectional"))
      (node (ref "U1") (pin "85") (pinfunction "P4[29]/TX_MCLK/MAT2[1]/RXD3_85") (pintype "bidirectional"))
    )
    (net (code "19") (name "ESPTX") (class "Default")
      (node (ref "U$1") (pin "D1") (pinfunction "URXD_D1") (pintype "bidirectional"))
      (node (ref "U1") (pin "82") (pinfunction "P4[28]/RX_MCLK/MAT2[0]/TXD3_82") (pintype "bidirectional"))
    )
    (net (code "20") (name "EXTRA1") (class "Default")
      (node (ref "R32") (pin "2") (pinfunction "2_2") (pintype "passive"))
      (node (ref "U1") (pin "40") (pinfunction "P1[26]/MCOB1/PWM1[6]/CAP0[0]_40") (pintype "bidirectional"))
    )
    (net (code "21") (name "EXTRA2") (class "Default")
      (node (ref "R34") (pin "2") (pinfunction "2_2") (pintype "passive"))
      (node (ref "U1") (pin "39") (pinfunction "P1[25]/MCOA1/MAT1[1]_39") (pintype "bidirectional"))
    )
    (net (code "22") (name "FANMOSFET") (class "Default")
      (node (ref "U3") (pin "11") (pinfunction "Y4_11") (pintype "output"))
      (node (ref "U6") (pin "1") (pinfunction "G_1") (pintype "passive"))
      (node (ref "U7") (pin "1") (pinfunction "G_1") (pintype "passive"))
    )
    (net (code "23") (name "FANPWM") (class "Default")
      (node (ref "R23") (pin "1") (pinfunction "1_1") (pintype "passive"))
      (node (ref "U1") (pin "70") (pinfunction "P2[3]/PWM1[4]/DCD1/TRACEDATA[2]_70") (pintype "bidirectional"))
      (node (ref "U3") (pin "12") (pinfunction "A4_12") (pintype "input"))
    )
    (net (code "24") (name "GND") (class "Default")
      (node (ref "C19") (pin "1") (pinfunction "1_1") (pintype "passive"))
      (node (ref "C20") (pin "1") (pinfunction "1_1") (pintype "passive"))
      (node (ref "C21") (pin "2") (pinfunction "2_2") (pintype "passive"))
      (node (ref "C25") (pin "2") (pinfunction "2_2") (pintype "passive"))
      (node (ref "C26") (pin "2") (pinfunction "2_2") (pintype "passive"))
      (node (ref "C27") (pin "2") (pinfunction "2_2") (pintype "passive"))
      (node (ref "C28") (pin "-") (pinfunction "-_-") (pintype "passive"))
      (node (ref "C29") (pin "2") (pinfunction "2_2") (pintype "passive"))
      (node (ref "C30") (pin "-") (pinfunction "-_-") (pintype "passive"))
      (node (ref "C32") (pin "1") (pinfunction "1_1") (pintype "passive"))
      (node (ref "C33") (pin "1") (pinfunction "1_1") (pintype "passive"))
      (node (ref "C34") (pin "1") (pinfunction "1_1") (pintype "passive"))
      (node (ref "C35") (pin "1") (pinfunction "1_1") (pintype "passive"))
      (node (ref "C36") (pin "1") (pinfunction "1_1") (pintype "passive"))
      (node (ref "C37") (pin "1") (pinfunction "1_1") (pintype "passive"))
      (node (ref "C38") (pin "1") (pinfunction "1_1") (pintype "passive"))
      (node (ref "C39") (pin "1") (pinfunction "1_1") (pintype "passive"))
      (node (ref "C40") (pin "2") (pinfunction "2_2") (pintype "passive"))
      (node (ref "C41") (pin "1") (pinfunction "1_1") (pintype "passive"))
      (node (ref "C42") (pin "1") (pinfunction "1_1") (pintype "passive"))
      (node (ref "C6") (pin "2") (pinfunction "2_2") (pintype "passive"))
      (node (ref "C8") (pin "1") (pinfunction "1_1") (pintype "passive"))
      (node (ref "C9") (pin "2") (pinfunction "2_2") (pintype "passive"))
      (node (ref "D2") (pin "A") (pinfunction "A_A") (pintype "passive"))
      (node (ref "EXP1") (pin "9") (pinfunction "KL_9") (pintype "passive"))
      (node (ref "EXP2") (pin "9") (pinfunction "KL_9") (pintype "passive"))
      (node (ref "EXPANSION3") (pin "1") (pinfunction "1_1") (pintype "passive"))
      (node (ref "EXPANSION3") (pin "2") (pinfunction "2_2") (pintype "passive"))
      (node (ref "EXTRA1") (pin "2") (pinfunction "2_2") (pintype "passive"))
      (node (ref "EXTRA2") (pin "2") (pinfunction "2_2") (pintype "passive"))
      (node (ref "EXTRA3") (pin "2") (pinfunction "2_2") (pintype "passive"))
      (node (ref "FANS") (pin "2") (pinfunction "2_2") (pintype "passive"))
      (node (ref "FANS") (pin "4") (pinfunction "4_4") (pintype "passive"))
      (node (ref "IC2") (pin "1") (pinfunction "GND_1") (pintype "input"))
      (node (ref "IC3") (pin "3") (pinfunction "GND_3") (pintype "power_in"))
      (node (ref "IC3") (pin "5") (pinfunction "~{ON}/OFF_5") (pintype "input"))
      (node (ref "JP1") (pin "1") (pinfunction "1_1") (pintype "passive"))
      (node (ref "JP2") (pin "3") (pinfunction "3_3") (pintype "passive"))
      (node (ref "L4") (pin "1") (pinfunction "1_1") (pintype "passive"))
      (node (ref "LED1") (pin "K") (pinfunction "C_K") (pintype "passive"))
      (node (ref "MOSFET1") (pin "3") (pinfunction "S_3") (pintype "passive"))
      (node (ref "NEOPIXEL") (pin "2") (pinfunction "2_2") (pintype "passive"))
      (node (ref "POWER") (pin "2") (pinfunction "KL_2") (pintype "passive"))
      (node (ref "R17") (pin "2") (pinfunction "2_2") (pintype "passive"))
      (node (ref "R20") (pin "2") (pinfunction "2_2") (pintype "passive"))
      (node (ref "R21") (pin "2") (pinfunction "2_2") (pintype "passive"))
      (node (ref "R22") (pin "2") (pinfunction "2_2") (pintype "passive"))
      (node (ref "R23") (pin "2") (pinfunction "2_2") (pintype "passive"))
      (node (ref "R9") (pin "2") (pinfunction "2_2") (pintype "passive"))
      (node (ref "RV3") (pin "1") (pinfunction "1_1") (pintype "passive"))
      (node (ref "RV4") (pin "2") (pinfunction "2_2") (pintype "passive"))
      (node (ref "RV5") (pin "2") (pinfunction "2_2") (pintype "passive"))
      (node (ref "RV6") (pin "2") (pinfunction "2_2") (pintype "passive"))
      (node (ref "RV7") (pin "2") (pinfunction "2_2") (pintype "passive"))
      (node (ref "RV8") (pin "2") (pinfunction "2_2") (pintype "passive"))
      (node (ref "S1") (pin "3") (pinfunction "P_3") (pintype "passive"))
      (node (ref "SERVO") (pin "2") (pinfunction "2_2") (pintype "passive"))
      (node (ref "SV1") (pin "4") (pinfunction "4_4") (pintype "passive"))
      (node (ref "SV2") (pin "2") (pinfunction "2_2") (pintype "passive"))
      (node (ref "SV3") (pin "2") (pinfunction "2_2") (pintype "passive"))
      (node (ref "SV3") (pin "4") (pinfunction "4_4") (pintype "passive"))
      (node (ref "SV3") (pin "6") (pinfunction "6_6") (pintype "passive"))
      (node (ref "SV5") (pin "16") (pinfunction "16_16") (pintype "passive"))
      (node (ref "SV5") (pin "4") (pinfunction "4_4") (pintype "passive"))
      (node (ref "U$1") (pin "A1") (pinfunction "GND_A1") (pintype "power_in"))
      (node (ref "U1") (pin "31") (pinfunction "VSS_2_31") (pintype "power_in"))
      (node (ref "U1") (pin "41") (pinfunction "VSS_3_41") (pintype "power_in"))
      (node (ref "U1") (pin "55") (pinfunction "VSS_4_55") (pintype "power_in"))
      (node (ref "U1") (pin "72") (pinfunction "VSS_5_72") (pintype "power_in"))
      (node (ref "U1") (pin "83") (pinfunction "VSS_6_83") (pintype "power_in"))
      (node (ref "U1") (pin "97") (pinfunction "VSS_97") (pintype "power_in"))
      (node (ref "U3") (pin "1") (pinfunction "OE1_1") (pintype "input"))
      (node (ref "U3") (pin "10") (pinfunction "OE3_10") (pintype "input"))
      (node (ref "U3") (pin "13") (pinfunction "OE4_13") (pintype "input"))
      (node (ref "U3") (pin "4") (pinfunction "OE2_4") (pintype "input"))
      (node (ref "U3") (pin "7") (pinfunction "GND_7") (pintype "power_in"))
      (node (ref "U4") (pin "2") (pinfunction "S_2") (pintype "passive"))
      (node (ref "U5") (pin "2") (pinfunction "S_2") (pintype "passive"))
      (node (ref "U6") (pin "2") (pinfunction "S_2") (pintype "passive"))
      (node (ref "U7") (pin "2") (pinfunction "S_2") (pintype "passive"))
      (node (ref "X1") (pin "1") (pinfunction "1_1") (pintype "passive"))
      (node (ref "XSTOP") (pin "2") (pinfunction "2_2") (pintype "passive"))
      (node (ref "YSTOP") (pin "2") (pinfunction "2_2") (pintype "passive"))
      (node (ref "ZSTOP") (pin "2") (pinfunction "2_2") (pintype "passive"))
    )
    (net (code "25") (name "HA1") (class "Default")
      (node (ref "IC1") (pin "41") (pinfunction "HA1_41") (pintype "output"))
      (node (ref "Q4") (pin "1") (pinfunction "G1_1") (pintype "passive"))
    )
    (net (code "26") (name "HA2") (class "Default")
      (node (ref "IC1") (pin "36") (pinfunction "HA2_36") (pintype "output"))
      (node (ref "Q4") (pin "8") (pinfunction "G2_8") (pintype "passive"))
    )
    (net (code "27") (name "HB1") (class "Default")
      (node (ref "IC1") (pin "1") (pinfunction "HB1_1") (pintype "output"))
      (node (ref "Q2") (pin "1") (pinfunction "G1_1") (pintype "passive"))
    )
    (net (code "28") (name "HB2") (class "Default")
      (node (ref "IC1") (pin "44") (pinfunction "HB2_44") (pintype "output"))
      (node (ref "Q2") (pin "8") (pinfunction "G2_8") (pintype "passive"))
    )
    (net (code "29") (name "HBMOSFET") (class "Default")
      (node (ref "MOSFET1") (pin "1") (pinfunction "G_1") (pintype "passive"))
      (node (ref "U3") (pin "8") (pinfunction "Y3_8") (pintype "output"))
    )
    (net (code "30") (name "HBPWM") (class "Default")
      (node (ref "R20") (pin "1") (pinfunction "1_1") (pintype "passive"))
      (node (ref "U1") (pin "68") (pinfunction "P2[5]/PWM1[6]/DTR1/TRACEDATA[0]_68") (pintype "bidirectional"))
      (node (ref "U3") (pin "9") (pinfunction "A3_9") (pintype "input"))
    )
    (net (code "31") (name "HEMOSFET1") (class "Default")
      (node (ref "U3") (pin "6") (pinfunction "Y2_6") (pintype "output"))
      (node (ref "U5") (pin "1") (pinfunction "G_1") (pintype "passive"))
    )
    (net (code "32") (name "HEMOSFET2") (class "Default")
      (node (ref "U3") (pin "3") (pinfunction "Y1_3") (pintype "output"))
      (node (ref "U4") (pin "1") (pinfunction "G_1") (pintype "passive"))
    )
    (net (code "33") (name "HEPWM1") (class "Default")
      (node (ref "R21") (pin "1") (pinfunction "1_1") (pintype "passive"))
      (node (ref "U1") (pin "66") (pinfunction "P2[7]/RD2/RTS1_66") (pintype "bidirectional"))
      (node (ref "U3") (pin "5") (pinfunction "A2_5") (pintype "input"))
    )
    (net (code "34") (name "HEPWM2") (class "Default")
      (node (ref "R22") (pin "1") (pinfunction "1_1") (pintype "passive"))
      (node (ref "U1") (pin "69") (pinfunction "P2[4]/PWM1[5]/DSR1/TRACEDATA[1]_69") (pintype "bidirectional"))
      (node (ref "U3") (pin "2") (pinfunction "A1_2") (pintype "input"))
    )
    (net (code "35") (name "LA1") (class "Default")
      (node (ref "IC1") (pin "39") (pinfunction "LA1_39") (pintype "output"))
      (node (ref "Q3") (pin "1") (pinfunction "G1_1") (pintype "passive"))
    )
    (net (code "36") (name "LA2") (class "Default")
      (node (ref "IC1") (pin "38") (pinfunction "LA2_38") (pintype "output"))
      (node (ref "Q3") (pin "8") (pinfunction "G2_8") (pintype "passive"))
    )
    (net (code "37") (name "LB1") (class "Default")
      (node (ref "IC1") (pin "47") (pinfunction "LB1_47") (pintype "output"))
      (node (ref "Q1") (pin "1") (pinfunction "G1_1") (pintype "passive"))
    )
    (net (code "38") (name "LB2") (class "Default")
      (node (ref "IC1") (pin "46") (pinfunction "LB2_46") (pintype "output"))
      (node (ref "Q1") (pin "8") (pinfunction "G2_8") (pintype "passive"))
    )
    (net (code "39") (name "MISO") (class "Default")
      (node (ref "EXPANSION3") (pin "5") (pinfunction "5_5") (pintype "passive"))
      (node (ref "U1") (pin "77") (pinfunction "P0[8]/I2STX_WS/MISO1/MAT2[2]_77") (pintype "bidirectional"))
    )
    (net (code "40") (name "MOSI") (class "Default")
      (node (ref "EXPANSION3") (pin "3") (pinfunction "3_3") (pintype "passive"))
      (node (ref "U1") (pin "76") (pinfunction "P0[9]/I2STX_SDA/MOSI1/MAT2[3]_76") (pintype "bidirectional"))
    )
    (net (code "41") (name "N$1") (class "Default")
      (node (ref "EXP1") (pin "1") (pinfunction "KL_1") (pintype "passive"))
      (node (ref "U1") (pin "21") (pinfunction "P1[30]/VBUS/AD0[4]_21") (pintype "bidirectional"))
    )
    (net (code "42") (name "N$2") (class "Default")
      (node (ref "EXP1") (pin "2") (pinfunction "KL_2") (pintype "passive"))
      (node (ref "U1") (pin "24") (pinfunction "P0[28]/SCL0/USB_SCL_24") (pintype "bidirectional"))
    )
    (net (code "43") (name "N$3") (class "Default")
      (node (ref "EXP1") (pin "3") (pinfunction "KL_3") (pintype "passive"))
      (node (ref "U1") (pin "32") (pinfunction "P1[18]/USB_UP_LED/PWM1[1]/CAP1[0]_32") (pintype "bidirectional"))
    )
    (net (code "44") (name "N$4") (class "Default")
      (node (ref "EXP1") (pin "4") (pinfunction "KL_4") (pintype "passive"))
      (node (ref "U1") (pin "33") (pinfunction "P1[19]/MCOA0/~{USB_PPWR/CAP1[1]}_33") (pintype "bidirectional"))
    )
    (net (code "45") (name "N$5") (class "Default")
      (node (ref "EXP1") (pin "5") (pinfunction "KL_5") (pintype "passive"))
      (node (ref "U1") (pin "34") (pinfunction "P1[20]/MCI0/PWM1[2]/SCK0_34") (pintype "bidirectional"))
    )
    (net (code "46") (name "N$6") (class "Default")
      (node (ref "EXP1") (pin "6") (pinfunction "KL_6") (pintype "passive"))
      (node (ref "U1") (pin "35") (pinfunction "P1[21]/~{MCABORT/PWM1[3]/SSEL0}_35") (pintype "bidirectional"))
    )
    (net (code "47") (name "N$7") (class "Default")
      (node (ref "EXP1") (pin "7") (pinfunction "KL_7") (pintype "passive"))
      (node (ref "U1") (pin "36") (pinfunction "P1[22]/MCOB0/USB_PWRD/MAT1[0]_36") (pintype "bidirectional"))
    )
    (net (code "48") (name "N$8") (class "Default")
      (node (ref "EXP1") (pin "8") (pinfunction "KL_8") (pintype "passive"))
      (node (ref "U1") (pin "37") (pinfunction "P1[23]/MCI1/PWM1[4]/MISO0_37") (pintype "bidirectional"))
    )
    (net (code "49") (name "N$11") (class "Default")
      (node (ref "EXP2") (pin "1") (pinfunction "KL_1") (pintype "passive"))
      (node (ref "U1") (pin "61") (pinfunction "P0[17]/CTS1/MISO0/MISO_61") (pintype "bidirectional"))
    )
    (net (code "50") (name "N$12") (class "Default")
      (node (ref "EXP2") (pin "2") (pinfunction "KL_2") (pintype "passive"))
      (node (ref "U1") (pin "62") (pinfunction "P0[15]/TXD1/SCK0/SCK_62") (pintype "bidirectional"))
    )
    (net (code "51") (name "N$13") (class "Default")
      (node (ref "EXP2") (pin "3") (pinfunction "KL_3") (pintype "passive"))
      (node (ref "U1") (pin "26") (pinfunction "P3[26]/STCLK/MAT0[1]/PWM1[3]_26") (pintype "bidirectional"))
    )
    (net (code "52") (name "N$14") (class "Default")
      (node (ref "EXP2") (pin "4") (pinfunction "KL_4") (pintype "passive"))
      (node (ref "U1") (pin "63") (pinfunction "P0[16]/RXD1/SSEL0/SSEL_63") (pintype "bidirectional"))
    )
    (net (code "53") (name "N$15") (class "Default")
      (node (ref "EXP2") (pin "5") (pinfunction "KL_5") (pintype "passive"))
      (node (ref "U1") (pin "27") (pinfunction "P3[25]/MAT0[0]/PWM1[2]_27") (pintype "bidirectional"))
    )
    (net (code "54") (name "N$16") (class "Default")
      (node (ref "EXP2") (pin "6") (pinfunction "KL_6") (pintype "passive"))
      (node (ref "U1") (pin "60") (pinfunction "P0[18]/DCD1/MOSI0/MOSI_60") (pintype "bidirectional"))
    )
    (net (code "55") (name "N$17") (class "Default")
      (node (ref "EXP2") (pin "7") (pinfunction "KL_7") (pintype "passive"))
      (node (ref "U1") (pin "20") (pinfunction "P1[31]/SCK1/AD0[5]_20") (pintype "bidirectional"))
    )
    (net (code "56") (name "N$41") (class "Default")
      (node (ref "HOTEND") (pin "4") (pinfunction "KL_4") (pintype "passive"))
      (node (ref "U4") (pin "3") (pinfunction "D_3") (pintype "passive"))
    )
    (net (code "57") (name "N$51") (class "Default")
      (node (ref "R26") (pin "1") (pinfunction "1_1") (pintype "passive"))
      (node (ref "R27") (pin "1") (pinfunction "1_1") (pintype "passive"))
      (node (ref "RV4") (pin "1") (pinfunction "1_1") (pintype "passive"))
      (node (ref "XSTOP") (pin "1") (pinfunction "1_1") (pintype "passive"))
    )
    (net (code "58") (name "N$52") (class "Default")
      (node (ref "EXTRA1") (pin "1") (pinfunction "1_1") (pintype "passive"))
      (node (ref "R32") (pin "1") (pinfunction "1_1") (pintype "passive"))
      (node (ref "R33") (pin "1") (pinfunction "1_1") (pintype "passive"))
      (node (ref "RV7") (pin "1") (pinfunction "1_1") (pintype "passive"))
    )
    (net (code "59") (name "N$55") (class "Default")
      (node (ref "R28") (pin "1") (pinfunction "1_1") (pintype "passive"))
      (node (ref "R29") (pin "1") (pinfunction "1_1") (pintype "passive"))
      (node (ref "RV5") (pin "1") (pinfunction "1_1") (pintype "passive"))
      (node (ref "YSTOP") (pin "1") (pinfunction "1_1") (pintype "passive"))
    )
    (net (code "60") (name "N$56") (class "Default")
      (node (ref "R30") (pin "1") (pinfunction "1_1") (pintype "passive"))
      (node (ref "R31") (pin "1") (pinfunction "1_1") (pintype "passive"))
      (node (ref "RV6") (pin "1") (pinfunction "1_1") (pintype "passive"))
      (node (ref "ZSTOP") (pin "1") (pinfunction "1_1") (pintype "passive"))
    )
    (net (code "61") (name "N$61") (class "Default")
      (node (ref "EXTRA2") (pin "1") (pinfunction "1_1") (pintype "passive"))
      (node (ref "R34") (pin "1") (pinfunction "1_1") (pintype "passive"))
      (node (ref "R35") (pin "1") (pinfunction "1_1") (pintype "passive"))
      (node (ref "RV8") (pin "1") (pinfunction "1_1") (pintype "passive"))
    )
    (net (code "62") (name "NPOWER") (class "Default")
      (node (ref "C8") (pin "2") (pinfunction "2_2") (pintype "passive"))
      (node (ref "NEOPIXEL") (pin "3") (pinfunction "3_3") (pintype "passive"))
      (node (ref "SERVO") (pin "3") (pinfunction "3_3") (pintype "passive"))
      (node (ref "SV1") (pin "5") (pinfunction "5_5") (pintype "passive"))
      (node (ref "SW2") (pin "5") (pinfunction "5_5") (pintype "passive"))
    )
    (net (code "63") (name "Net-(HEATBEDA-KL)") (class "Default")
      (node (ref "HEATBED") (pin "1") (pinfunction "KL_1") (pintype "passive"))
      (node (ref "MOSFET1") (pin "2") (pinfunction "D_2") (pintype "passive"))
    )
    (net (code "64") (name "Net-(HOTENDB-KL)") (class "Default")
      (node (ref "HOTEND") (pin "2") (pinfunction "KL_2") (pintype "passive"))
      (node (ref "U5") (pin "3") (pinfunction "D_3") (pintype "passive"))
    )
    (net (code "65") (name "Net-(IC1-5VOUT)") (class "Default")
      (node (ref "C17") (pin "2") (pinfunction "2_2") (pintype "passive"))
      (node (ref "IC1") (pin "5") (pinfunction "5VOUT_5") (pintype "bidirectional"))
      (node (ref "R3") (pin "2") (pinfunction "2_2") (pintype "passive"))
    )
    (net (code "66") (name "Net-(IC1-12VOUT)") (class "Default")
      (node (ref "C7") (pin "2") (pinfunction "2_2") (pintype "passive"))
      (node (ref "IC1") (pin "3") (pinfunction "12VOUT_3") (pintype "bidirectional"))
    )
    (net (code "67") (name "Net-(IC1-CPI)") (class "Default")
      (node (ref "C3") (pin "2") (pinfunction "2_2") (pintype "passive"))
      (node (ref "IC1") (pin "32") (pinfunction "CPI_32") (pintype "input"))
    )
    (net (code "68") (name "Net-(IC1-CPO)") (class "Default")
      (node (ref "C3") (pin "1") (pinfunction "1_1") (pintype "passive"))
      (node (ref "IC1") (pin "31") (pinfunction "CPO_31") (pintype "input"))
    )
    (net (code "69") (name "Net-(IC1-VCC)") (class "Default")
      (node (ref "C4") (pin "2") (pinfunction "2_2") (pintype "passive"))
      (node (ref "IC1") (pin "29") (pinfunction "VCC_29") (pintype "power_in"))
      (node (ref "R3") (pin "1") (pinfunction "1_1") (pintype "passive"))
    )
    (net (code "70") (name "Net-(IC1-VCP)") (class "Default")
      (node (ref "C10") (pin "1") (pinfunction "1_1") (pintype "passive"))
      (node (ref "IC1") (pin "34") (pinfunction "VCP_34") (pintype "input"))
    )
    (net (code "71") (name "Net-(IC3-FB)") (class "Default")
      (node (ref "C31") (pin "1") (pinfunction "1_1") (pintype "passive"))
      (node (ref "IC3") (pin "4") (pinfunction "FB_4") (pintype "input"))
      (node (ref "R17") (pin "1") (pinfunction "1_1") (pintype "passive"))
      (node (ref "R18") (pin "S") (pinfunction "S_S") (pintype "passive"))
    )
    (net (code "72") (name "Net-(IC3-OUT)") (class "Default")
      (node (ref "D2") (pin "C") (pinfunction "C_C") (pintype "passive"))
      (node (ref "IC3") (pin "2") (pinfunction "OUT_2") (pintype "output"))
      (node (ref "L1") (pin "2") (pinfunction "2_2") (pintype "passive"))
    )
    (net (code "73") (name "Net-(IC3-VIN)") (class "Default")
      (node (ref "C28") (pin "+") (pinfunction "+_+") (pintype "passive"))
      (node (ref "C29") (pin "1") (pinfunction "1_1") (pintype "passive"))
      (node (ref "D1") (pin "C") (pinfunction "C_C") (pintype "passive"))
      (node (ref "IC3") (pin "1") (pinfunction "VIN_1") (pintype "input"))
    )
    (net (code "74") (name "Net-(Q1-S1)") (class "Default")
      (node (ref "Q1") (pin "4") (pinfunction "S1_4") (pintype "passive"))
      (node (ref "Q1") (pin "5") (pinfunction "S2_5") (pintype "passive"))
      (node (ref "R1") (pin "2") (pinfunction "2_2") (pintype "passive"))
      (node (ref "R2") (pin "1") (pinfunction "1_1") (pintype "passive"))
    )
    (net (code "75") (name "Net-(Q3-S1)") (class "Default")
      (node (ref "Q3") (pin "4") (pinfunction "S1_4") (pintype "passive"))
      (node (ref "Q3") (pin "5") (pinfunction "S2_5") (pintype "passive"))
      (node (ref "R10") (pin "1") (pinfunction "1_1") (pintype "passive"))
      (node (ref "R6") (pin "2") (pinfunction "2_2") (pintype "passive"))
    )
    (net (code "76") (name "Net-(Q5-D)") (class "Default")
      (node (ref "Q5") (pin "3") (pinfunction "D_3") (pintype "passive"))
      (node (ref "R12") (pin "2") (pinfunction "2_2") (pintype "passive"))
    )
    (net (code "77") (name "Net-(U1-P2[1]{slash}PWM1[2]{slash}RXD1)") (class "Default")
      (node (ref "R37") (pin "2") (pinfunction "2_2") (pintype "passive"))
      (node (ref "U1") (pin "74") (pinfunction "P2[1]/PWM1[2]/RXD1_74") (pintype "bidirectional"))
    )
    (net (code "78") (name "Net-(U1-RTCX1)") (class "Default")
      (node (ref "R24") (pin "1") (pinfunction "1_1") (pintype "passive"))
      (node (ref "U1") (pin "16") (pinfunction "RTCX1_16") (pintype "input"))
    )
    (net (code "79") (name "Net-(U1-XTAL1)") (class "Default")
      (node (ref "C41") (pin "2") (pinfunction "2_2") (pintype "passive"))
      (node (ref "Q6") (pin "1") (pinfunction "1_1") (pintype "passive"))
      (node (ref "R25") (pin "2") (pinfunction "2_2") (pintype "passive"))
      (node (ref "U1") (pin "22") (pinfunction "XTAL1_22") (pintype "input"))
    )
    (net (code "80") (name "Net-(U1-XTAL2)") (class "Default")
      (node (ref "C42") (pin "2") (pinfunction "2_2") (pintype "passive"))
      (node (ref "Q6") (pin "2") (pinfunction "2_2") (pintype "passive"))
      (node (ref "R25") (pin "1") (pinfunction "1_1") (pintype "passive"))
      (node (ref "U1") (pin "23") (pinfunction "XTAL2_23") (pintype "output"))
    )
    (net (code "81") (name "Net-(U1-~{RSTOUT})") (class "Default")
      (node (ref "R19") (pin "1") (pinfunction "1_1") (pintype "passive"))
      (node (ref "U1") (pin "14") (pinfunction "~{RSTOUT}_14") (pintype "output"))
    )
    (net (code "82") (name "Net-(U2-VN)") (class "Default")
      (node (ref "C20") (pin "2") (pinfunction "2_2") (pintype "passive"))
      (node (ref "U2") (pin "2") (pinfunction "VN_2") (pintype "power_in"))
    )
    (net (code "83") (name "Net-(U6-D)") (class "Default")
      (node (ref "CONTROLLED-FANS") (pin "4") (pinfunction "4_4") (pintype "passive"))
      (node (ref "U6") (pin "3") (pinfunction "D_3") (pintype "passive"))
    )
    (net (code "84") (name "Net-(U7-D)") (class "Default")
      (node (ref "CONTROLLED-FANS") (pin "2") (pinfunction "2_2") (pintype "passive"))
      (node (ref "U7") (pin "3") (pinfunction "D_3") (pintype "passive"))
    )
    (net (code "85") (name "P0.26") (class "Default")
      (node (ref "EXPANSION3") (pin "7") (pinfunction "7_7") (pintype "passive"))
      (node (ref "U1") (pin "6") (pinfunction "P0[26]/AD0[3]/AOUT/RXD3_6") (pintype "bidirectional"))
    )
    (net (code "86") (name "P0.27") (class "Default")
      (node (ref "EXPANSION3") (pin "8") (pinfunction "8_8") (pintype "passive"))
      (node (ref "U1") (pin "25") (pinfunction "P0[27]/SDA0/USB_SDA_25") (pintype "bidirectional"))
    )
    (net (code "87") (name "P38") (class "Default")
      (node (ref "NEOPIXEL") (pin "1") (pinfunction "1_1") (pintype "passive"))
      (node (ref "U1") (pin "38") (pinfunction "P1[24]/MCI2/PWM1[5]/MOSI0_38") (pintype "bidirectional"))
    )
    (net (code "88") (name "POWERIN") (class "Default")
      (node (ref "F1") (pin "1A") (pinfunction "1A_1A") (pintype "passive"))
      (node (ref "F2") (pin "2A") (pinfunction "2A_2A") (pintype "passive"))
      (node (ref "POWER") (pin "1") (pinfunction "KL_1") (pintype "passive"))
    )
    (net (code "89") (name "PROBE") (class "Default")
      (node (ref "EXTRA3") (pin "1") (pinfunction "1_1") (pintype "passive"))
      (node (ref "U1") (pin "48") (pinfunction "P0[10]/TXD2/SDA2/MAT3[0]_48") (pintype "bidirectional"))
    )
    (net (code "90") (name "RESET") (class "Default")
      (node (ref "C21") (pin "1") (pinfunction "1_1") (pintype "passive"))
      (node (ref "EXP2") (pin "8") (pinfunction "KL_8") (pintype "passive"))
      (node (ref "R13") (pin "2") (pinfunction "2_2") (pintype "passive"))
      (node (ref "S1") (pin "1") (pinfunction "S_1") (pintype "passive"))
      (node (ref "SV1") (pin "1") (pinfunction "1_1") (pintype "passive"))
      (node (ref "U1") (pin "17") (pinfunction "~{RESET}_17") (pintype "input"))
    )
    (net (code "91") (name "RX0") (class "Default")
      (node (ref "SV1") (pin "2") (pinfunction "2_2") (pintype "passive"))
      (node (ref "U1") (pin "99") (pinfunction "P0[3]/RXD0/AD0[6]_99") (pintype "bidirectional"))
    )
    (net (code "92") (name "SCK") (class "Default")
      (node (ref "EXPANSION3") (pin "6") (pinfunction "6_6") (pintype "passive"))
      (node (ref "U1") (pin "78") (pinfunction "P0[7]/I2STX_CLK/SCK1/MAT2[1]_78") (pintype "bidirectional"))
    )
    (net (code "93") (name "SCL1") (class "Default")
      (node (ref "SV2") (pin "4") (pinfunction "4_4") (pintype "passive"))
      (node (ref "U1") (pin "47") (pinfunction "P0[1]/TD1/RXD3/SCL1_47") (pintype "bidirectional"))
    )
    (net (code "94") (name "SDA1") (class "Default")
      (node (ref "SV2") (pin "3") (pinfunction "3_3") (pintype "passive"))
      (node (ref "U1") (pin "46") (pinfunction "P0[0]/RD1/TXD3/SDA1_46") (pintype "bidirectional"))
    )
    (net (code "95") (name "SERVO") (class "Default")
      (node (ref "SERVO") (pin "1") (pinfunction "1_1") (pintype "passive"))
      (node (ref "U1") (pin "75") (pinfunction "P2[0]/PWM1[1]/TXD1_75") (pintype "bidirectional"))
    )
    (net (code "96") (name "SOFTCONNECT") (class "Default")
      (node (ref "Q5") (pin "1") (pinfunction "G_1") (pintype "passive"))
      (node (ref "R11") (pin "1") (pinfunction "1_1") (pintype "passive"))
      (node (ref "U1") (pin "64") (pinfunction "P2[9]/USB_CONNECT/RXD2_64") (pintype "bidirectional"))
    )
    (net (code "97") (name "SRAH") (class "Default")
      (node (ref "IC1") (pin "8") (pinfunction "SRAH_8") (pintype "input"))
      (node (ref "R6") (pin "1") (pinfunction "1_1") (pintype "passive"))
    )
    (net (code "98") (name "SRAL") (class "Default")
      (node (ref "IC1") (pin "7") (pinfunction "SRAL_7") (pintype "input"))
      (node (ref "R4") (pin "2") (pinfunction "2_2") (pintype "passive"))
    )
    (net (code "99") (name "SRBH") (class "Default")
      (node (ref "IC1") (pin "9") (pinfunction "SRBH_9") (pintype "input"))
      (node (ref "R1") (pin "1") (pinfunction "1_1") (pintype "passive"))
    )
    (net (code "100") (name "SRBL") (class "Default")
      (node (ref "IC1") (pin "10") (pinfunction "SRBL_10") (pintype "input"))
      (node (ref "R5") (pin "2") (pinfunction "2_2") (pintype "passive"))
    )
    (net (code "101") (name "SSEL") (class "Default")
      (node (ref "EXPANSION3") (pin "4") (pinfunction "4_4") (pintype "passive"))
      (node (ref "U1") (pin "79") (pinfunction "P0[6]/I2SRX_SDA/SSEL1/MAT2[0]_79") (pintype "bidirectional"))
    )
    (net (code "102") (name "SWDCLK") (class "Default")
      (node (ref "JP2") (pin "4") (pinfunction "4_4") (pintype "passive"))
      (node (ref "U1") (pin "5") (pinfunction "TCK/SWDCLK_5") (pintype "input"))
    )
    (net (code "103") (name "SWDIO") (class "Default")
      (node (ref "JP2") (pin "2") (pinfunction "2_2") (pintype "passive"))
      (node (ref "U1") (pin "3") (pinfunction "TMS/SWDIO_3") (pintype "bidirectional"))
    )
    (net (code "104") (name "TH1") (class "Default")
      (node (ref "C22") (pin "2") (pinfunction "2_2") (pintype "passive"))
      (node (ref "R14") (pin "2") (pinfunction "2_2") (pintype "passive"))
      (node (ref "RV") (pin "2") (pinfunction "2_2") (pintype "passive"))
      (node (ref "THERMISTOR1") (pin "1") (pinfunction "S_1") (pintype "passive"))
      (node (ref "U1") (pin "9") (pinfunction "P0[23]/AD0[0]/I2SRX_CLK/CAP3[0]_9") (pintype "bidirectional"))
    )
    (net (code "105") (name "TH2") (class "Default")
      (node (ref "C23") (pin "2") (pinfunction "2_2") (pintype "passive"))
      (node (ref "R15") (pin "2") (pinfunction "2_2") (pintype "passive"))
      (node (ref "RV1") (pin "2") (pinfunction "2_2") (pintype "passive"))
      (node (ref "THERMISTOR2") (pin "1") (pinfunction "S_1") (pintype "passive"))
      (node (ref "U1") (pin "8") (pinfunction "P0[24]/AD0[1]/I2SRX_WS/CAP3[1]_8") (pintype "bidirectional"))
    )
    (net (code "106") (name "THB") (class "Default")
      (node (ref "C24") (pin "2") (pinfunction "2_2") (pintype "passive"))
      (node (ref "R16") (pin "2") (pinfunction "2_2") (pintype "passive"))
      (node (ref "RV2") (pin "2") (pinfunction "2_2") (pintype "passive"))
      (node (ref "THERMISTOR3") (pin "1") (pinfunction "S_1") (pintype "passive"))
      (node (ref "U1") (pin "7") (pinfunction "P0[25]/AD0[2]/I2SRX_SDA/TXD3_7") (pintype "bidirectional"))
    )
    (net (code "107") (name "TRST") (class "Default")
      (node (ref "JP2") (pin "5") (pinfunction "5_5") (pintype "passive"))
      (node (ref "U1") (pin "4") (pinfunction "~{TRST}_4") (pintype "input"))
    )
    (net (code "108") (name "TX0") (class "Default")
      (node (ref "SV1") (pin "3") (pinfunction "3_3") (pintype "passive"))
      (node (ref "U1") (pin "98") (pinfunction "P0[2]/TXD0/AD0[7]_98") (pintype "bidirectional"))
    )
    (net (code "109") (name "UC3.3V") (class "Default")
      (node (ref "C33") (pin "2") (pinfunction "2_2") (pintype "passive"))
      (node (ref "C34") (pin "2") (pinfunction "2_2") (pintype "passive"))
      (node (ref "C35") (pin "2") (pinfunction "2_2") (pintype "passive"))
      (node (ref "C36") (pin "2") (pinfunction "2_2") (pintype "passive"))
      (node (ref "C37") (pin "2") (pinfunction "2_2") (pintype "passive"))
      (node (ref "C38") (pin "2") (pinfunction "2_2") (pintype "passive"))
      (node (ref "C39") (pin "2") (pinfunction "2_2") (pintype "passive"))
      (node (ref "L2") (pin "2") (pinfunction "2_2") (pintype "passive"))
      (node (ref "R19") (pin "2") (pinfunction "2_2") (pintype "passive"))
      (node (ref "R24") (pin "2") (pinfunction "2_2") (pintype "passive"))
      (node (ref "U1") (pin "19") (pinfunction "VBAT_19") (pintype "input"))
      (node (ref "U1") (pin "28") (pinfunction "VDD(3V3)_2_28") (pintype "power_in"))
      (node (ref "U1") (pin "42") (pinfunction "VDD(REG)(3V3)_2_42") (pintype "power_in"))
      (node (ref "U1") (pin "54") (pinfunction "VDD(3V3)_3_54") (pintype "power_in"))
      (node (ref "U1") (pin "71") (pinfunction "VDD(3V3)_4_71") (pintype "power_in"))
      (node (ref "U1") (pin "84") (pinfunction "VDD(REG)(3V3)_84") (pintype "power_in"))
      (node (ref "U1") (pin "96") (pinfunction "VDD(3V3)_96") (pintype "power_in"))
    )
    (net (code "110") (name "USB5V") (class "Default")
      (node (ref "C19") (pin "2") (pinfunction "2_2") (pintype "passive"))
      (node (ref "R9") (pin "1") (pinfunction "1_1") (pintype "passive"))
      (node (ref "SW1") (pin "1") (pinfunction "1_1") (pintype "passive"))
      (node (ref "U2") (pin "5") (pinfunction "VP_5") (pintype "power_in"))
      (node (ref "X1") (pin "4") (pinfunction "4_4") (pintype "passive"))
    )
    (net (code "111") (name "VBB") (class "Default")
      (node (ref "CONTROLLED-FANS") (pin "1") (pinfunction "1_1") (pintype "passive"))
      (node (ref "CONTROLLED-FANS") (pin "3") (pinfunction "3_3") (pintype "passive"))
      (node (ref "D1") (pin "A") (pinfunction "A_A") (pintype "passive"))
      (node (ref "F2") (pin "1A") (pinfunction "1A_1A") (pintype "passive"))
      (node (ref "FANS") (pin "1") (pinfunction "1_1") (pintype "passive"))
      (node (ref "FANS") (pin "3") (pinfunction "3_3") (pintype "passive"))
      (node (ref "HOTEND") (pin "1") (pinfunction "KL_1") (pintype "passive"))
      (node (ref "HOTEND") (pin "3") (pinfunction "KL_3") (pintype "passive"))
      (node (ref "SV3") (pin "1") (pinfunction "1_1") (pintype "passive"))
      (node (ref "SV3") (pin "3") (pinfunction "3_3") (pintype "passive"))
      (node (ref "SV3") (pin "5") (pinfunction "5_5") (pintype "passive"))
      (node (ref "SV5") (pin "2") (pinfunction "2_2") (pintype "passive"))
    )
    (net (code "112") (name "VDDA") (class "Default")
      (node (ref "C40") (pin "1") (pinfunction "1_1") (pintype "passive"))
      (node (ref "L3") (pin "2") (pinfunction "2_2") (pintype "passive"))
      (node (ref "R14") (pin "1") (pinfunction "1_1") (pintype "passive"))
      (node (ref "R15") (pin "1") (pinfunction "1_1") (pintype "passive"))
      (node (ref "R16") (pin "1") (pinfunction "1_1") (pintype "passive"))
      (node (ref "U1") (pin "10") (pinfunction "VDDA_10") (pintype "power_in"))
      (node (ref "U1") (pin "12") (pinfunction "VREFP_12") (pintype "power_in"))
    )
    (net (code "113") (name "VHEAT") (class "Default")
      (node (ref "F1") (pin "2A") (pinfunction "2A_2A") (pintype "passive"))
      (node (ref "HEATBED") (pin "2") (pinfunction "KL_2") (pintype "passive"))
    )
    (net (code "114") (name "VOT") (class "Default")
      (node (ref "JP1") (pin "2") (pinfunction "2_2") (pintype "passive"))
      (node (ref "SW2") (pin "4") (pinfunction "4_4") (pintype "passive"))
    )
    (net (code "115") (name "X-DIR") (class "Default")
      (node (ref "IC1") (pin "18") (pinfunction "REFR_DIR_18") (pintype "input"))
      (node (ref "SV4") (pin "1") (pinfunction "1_1") (pintype "passive"))
    )
    (net (code "116") (name "X-EN") (class "Default")
      (node (ref "R36") (pin "2") (pinfunction "2_2") (pintype "passive"))
      (node (ref "R37") (pin "1") (pinfunction "1_1") (pintype "passive"))
      (node (ref "SV4") (pin "16") (pinfunction "16_16") (pintype "passive"))
    )
    (net (code "117") (name "X-ENABLE") (class "Default")
      (node (ref "IC1") (pin "28") (pinfunction "DRV_ENN_28") (pintype "input"))
      (node (ref "SV4") (pin "15") (pinfunction "15_15") (pintype "passive"))
    )
    (net (code "118") (name "X-RX") (class "Default")
      (node (ref "IC1") (pin "13") (pinfunction "CSN_CFG3_13") (pintype "input"))
      (node (ref "SV4") (pin "9") (pinfunction "9_9") (pintype "passive"))
    )
    (net (code "119") (name "X-SLP") (class "Default")
      (node (ref "IC1") (pin "12") (pinfunction "CLK_12") (pintype "input"))
      (node (ref "SV4") (pin "5") (pinfunction "5_5") (pintype "passive"))
    )
    (net (code "120") (name "X-STP") (class "Default")
      (node (ref "IC1") (pin "17") (pinfunction "REFL_STEP_17") (pintype "input"))
      (node (ref "SV4") (pin "3") (pinfunction "3_3") (pintype "passive"))
    )
    (net (code "121") (name "X1A") (class "Default")
      (node (ref "SV5") (pin "10") (pinfunction "10_10") (pintype "passive"))
      (node (ref "SV6") (pin "2") (pinfunction "2_2") (pintype "passive"))
    )
    (net (code "122") (name "X1B") (class "Default")
      (node (ref "SV5") (pin "12") (pinfunction "12_12") (pintype "passive"))
      (node (ref "SV6") (pin "1") (pinfunction "1_1") (pintype "passive"))
    )
    (net (code "123") (name "X2A") (class "Default")
      (node (ref "SV5") (pin "8") (pinfunction "8_8") (pintype "passive"))
      (node (ref "SV6") (pin "3") (pinfunction "3_3") (pintype "passive"))
    )
    (net (code "124") (name "X2B") (class "Default")
      (node (ref "SV5") (pin "6") (pinfunction "6_6") (pintype "passive"))
      (node (ref "SV6") (pin "4") (pinfunction "4_4") (pintype "passive"))
    )
    (net (code "125") (name "XDIR") (class "Default")
      (node (ref "SV4") (pin "2") (pinfunction "2_2") (pintype "passive"))
      (node (ref "U1") (pin "67") (pinfunction "P2[6]/PCAP1[0]/RI1/TRACECLK_67") (pintype "bidirectional"))
    )
    (net (code "126") (name "XDRIVERGND") (class "Default")
      (node (ref "C1") (pin "2") (pinfunction "2_2") (pintype "passive"))
      (node (ref "C11") (pin "2") (pinfunction "2_2") (pintype "passive"))
      (node (ref "C12") (pin "2") (pinfunction "2_2") (pintype "passive"))
      (node (ref "C15") (pin "2") (pinfunction "2_2") (pintype "passive"))
      (node (ref "C17") (pin "1") (pinfunction "1_1") (pintype "passive"))
      (node (ref "C2") (pin "2") (pinfunction "2_2") (pintype "passive"))
      (node (ref "C4") (pin "1") (pinfunction "1_1") (pintype "passive"))
      (node (ref "C43") (pin "2") (pinfunction "2_2") (pintype "passive"))
      (node (ref "C5") (pin "2") (pinfunction "2_2") (pintype "passive"))
      (node (ref "C7") (pin "1") (pinfunction "1_1") (pintype "passive"))
      (node (ref "IC1") (pin "11") (pinfunction "TST_MODE_11") (pintype "input"))
      (node (ref "IC1") (pin "19") (pinfunction "GNDD_19") (pintype "power_in"))
      (node (ref "IC1") (pin "30") (pinfunction "GNDD_2_30") (pintype "power_in"))
      (node (ref "IC1") (pin "49") (pinfunction "GNDP_49") (pintype "power_in"))
      (node (ref "IC1") (pin "6") (pinfunction "GNDA_6") (pintype "power_in"))
      (node (ref "R10") (pin "2") (pinfunction "2_2") (pintype "passive"))
      (node (ref "R2") (pin "2") (pinfunction "2_2") (pintype "passive"))
      (node (ref "R4") (pin "1") (pinfunction "1_1") (pintype "passive"))
      (node (ref "R5") (pin "1") (pinfunction "1_1") (pintype "passive"))
      (node (ref "SV5") (pin "15") (pinfunction "15_15") (pintype "passive"))
      (node (ref "SV5") (pin "3") (pinfunction "3_3") (pintype "passive"))
    )
    (net (code "127") (name "XDRIVERVBB") (class "Default")
      (node (ref "C1") (pin "1") (pinfunction "1_1") (pintype "passive"))
      (node (ref "C10") (pin "2") (pinfunction "2_2") (pintype "passive"))
      (node (ref "C12") (pin "1") (pinfunction "1_1") (pintype "passive"))
      (node (ref "C15") (pin "1") (pinfunction "1_1") (pintype "passive"))
      (node (ref "C2") (pin "1") (pinfunction "1_1") (pintype "passive"))
      (node (ref "C43") (pin "1") (pinfunction "1_1") (pintype "passive"))
      (node (ref "C5") (pin "1") (pinfunction "1_1") (pintype "passive"))
      (node (ref "IC1") (pin "33") (pinfunction "VS_33") (pintype "power_in"))
      (node (ref "IC1") (pin "4") (pinfunction "VSA_4") (pintype "power_in"))
      (node (ref "Q2") (pin "10") (pinfunction "D1_10") (pintype "passive"))
      (node (ref "Q2") (pin "9") (pinfunction "D2_9") (pintype "passive"))
      (node (ref "Q4") (pin "10") (pinfunction "D1_10") (pintype "passive"))
      (node (ref "Q4") (pin "9") (pinfunction "D2_9") (pintype "passive"))
      (node (ref "SV5") (pin "1") (pinfunction "1_1") (pintype "passive"))
    )
    (net (code "128") (name "XDRIVERVSS") (class "Default")
      (node (ref "C11") (pin "1") (pinfunction "1_1") (pintype "passive"))
      (node (ref "IC1") (pin "20") (pinfunction "VCC_IO_20") (pintype "power_in"))
      (node (ref "IC1") (pin "21") (pinfunction "SD_MODE_21") (pintype "input"))
      (node (ref "IC1") (pin "22") (pinfunction "SPI_MODE_22") (pintype "input"))
      (node (ref "SV5") (pin "13") (pinfunction "13_13") (pintype "passive"))
    )
    (net (code "129") (name "XMIN") (class "Default")
      (node (ref "R26") (pin "2") (pinfunction "2_2") (pintype "passive"))
      (node (ref "U1") (pin "45") (pinfunction "P1[29]/MCOB2/PCAP1[1]/MAT0[1]_45") (pintype "bidirectional"))
    )
    (net (code "130") (name "XMISO") (class "Default")
      (node (ref "SV4") (pin "8") (pinfunction "8_8") (pintype "passive"))
      (node (ref "U1") (pin "80") (pinfunction "P0[5]/I2SRX_WS/TD2/CAP2[1]_80") (pintype "bidirectional"))
    )
    (net (code "131") (name "XMOSI") (class "Default")
      (node (ref "SV4") (pin "14") (pinfunction "14_14") (pintype "passive"))
      (node (ref "U1") (pin "86") (pinfunction "P1[17]/ENET_MDIO_86") (pintype "bidirectional"))
    )
    (net (code "132") (name "XMOTORMISO") (class "Default")
      (node (ref "IC1") (pin "16") (pinfunction "SDO_CFG0_16") (pintype "output"))
      (node (ref "SV4") (pin "7") (pinfunction "7_7") (pintype "passive"))
    )
    (net (code "133") (name "XMOTORMOSI") (class "Default")
      (node (ref "IC1") (pin "15") (pinfunction "SDI_CFG1_15") (pintype "input"))
      (node (ref "SV4") (pin "13") (pinfunction "13_13") (pintype "passive"))
    )
    (net (code "134") (name "XMOTORSCK") (class "Default")
      (node (ref "IC1") (pin "14") (pinfunction "SCK_CFG2_14") (pintype "input"))
      (node (ref "SV4") (pin "11") (pinfunction "11_11") (pintype "passive"))
    )
    (net (code "135") (name "XRX") (class "Default")
      (node (ref "SV4") (pin "10") (pinfunction "10_10") (pintype "passive"))
      (node (ref "U1") (pin "90") (pinfunction "P1[10]/ENET_RXD1_90") (pintype "bidirectional"))
    )
    (net (code "136") (name "XSCK") (class "Default")
      (node (ref "SV4") (pin "12") (pinfunction "12_12") (pintype "passive"))
      (node (ref "U1") (pin "81") (pinfunction "P0[4]/I2SRX_CLK/RD2/CAP2[0]_81") (pintype "bidirectional"))
    )
    (net (code "137") (name "XSLP") (class "Default")
      (node (ref "SV4") (pin "6") (pinfunction "6_6") (pintype "passive"))
    )
    (net (code "138") (name "XSTP") (class "Default")
      (node (ref "SV4") (pin "4") (pinfunction "4_4") (pintype "passive"))
      (node (ref "U1") (pin "73") (pinfunction "P2[2]/PWM1[3]/CTS1/TRACEDATA[3]_73") (pintype "bidirectional"))
    )
    (net (code "139") (name "YMIN") (class "Default")
      (node (ref "R28") (pin "2") (pinfunction "2_2") (pintype "passive"))
      (node (ref "U1") (pin "44") (pinfunction "P1[28]/MCOA2/PCAP1[0]/MAT0[0]_44") (pintype "bidirectional"))
    )
    (net (code "140") (name "ZMIN") (class "Default")
      (node (ref "R30") (pin "2") (pinfunction "2_2") (pintype "passive"))
      (node (ref "U1") (pin "43") (pinfunction "P1[27]/CLKOUT/~{USB_OVRCR/CAP0[1]}_43") (pintype "bidirectional"))
    )
    (net (code "141") (name "unconnected-(EXP2B-KL-Pad10)") (class "Default")
      (node (ref "EXP2") (pin "10") (pinfunction "KL_10") (pintype "passive"))
    )
    (net (code "142") (name "unconnected-(F1-Pad1B)") (class "Default")
      (node (ref "F1") (pin "1B") (pinfunction "1B_1B") (pintype "passive"))
    )
    (net (code "143") (name "unconnected-(F1-Pad2B)") (class "Default")
      (node (ref "F1") (pin "2B") (pinfunction "2B_2B") (pintype "passive"))
    )
    (net (code "144") (name "unconnected-(F2-Pad1B)") (class "Default")
      (node (ref "F2") (pin "1B") (pinfunction "1B_1B") (pintype "passive"))
    )
    (net (code "145") (name "unconnected-(F2-Pad2B)") (class "Default")
      (node (ref "F2") (pin "2B") (pinfunction "2B_2B") (pintype "passive"))
    )
    (net (code "146") (name "unconnected-(F3-Pad1B)") (class "Default")
      (node (ref "F3") (pin "1B") (pinfunction "1B_1B") (pintype "passive"))
    )
    (net (code "147") (name "unconnected-(F3-Pad2B)") (class "Default")
      (node (ref "F3") (pin "2B") (pinfunction "2B_2B") (pintype "passive"))
    )
    (net (code "148") (name "unconnected-(IC1-DIAG0_SWN-Pad26)") (class "Default")
      (node (ref "IC1") (pin "26") (pinfunction "DIAG0_SWN_26") (pintype "bidirectional"))
    )
    (net (code "149") (name "unconnected-(IC1-DIAG1_SWP-Pad27)") (class "Default")
      (node (ref "IC1") (pin "27") (pinfunction "DIAG1_SWP_27") (pintype "bidirectional"))
    )
    (net (code "150") (name "unconnected-(IC1-ENCA_CFG5-Pad24)") (class "Default")
      (node (ref "IC1") (pin "24") (pinfunction "ENCA_CFG5_24") (pintype "input"))
    )
    (net (code "151") (name "unconnected-(IC1-ENCB_CFG4-Pad23)") (class "Default")
      (node (ref "IC1") (pin "23") (pinfunction "ENCB_CFG4_23") (pintype "input"))
    )
    (net (code "152") (name "unconnected-(IC1-ENCN_CFG6-Pad25)") (class "Default")
      (node (ref "IC1") (pin "25") (pinfunction "ENCN_CFG6_25") (pintype "input"))
    )
    (net (code "153") (name "unconnected-(R18-PadE)") (class "Default")
      (node (ref "R18") (pin "E") (pinfunction "E_E") (pintype "passive"))
    )
    (net (code "154") (name "unconnected-(S1-P1-Pad4)") (class "Default")
      (node (ref "S1") (pin "4") (pinfunction "P1_4") (pintype "passive"))
    )
    (net (code "155") (name "unconnected-(S1-S1-Pad2)") (class "Default")
      (node (ref "S1") (pin "2") (pinfunction "S1_2") (pintype "passive"))
    )
    (net (code "156") (name "unconnected-(SW1-Pad4)") (class "Default")
      (node (ref "SW1") (pin "4") (pinfunction "4_4") (pintype "passive"))
    )
    (net (code "157") (name "unconnected-(SW1-Pad5)") (class "Default")
      (node (ref "SW1") (pin "5") (pinfunction "5_5") (pintype "passive"))
    )
    (net (code "158") (name "unconnected-(SW1-Pad6)") (class "Default")
      (node (ref "SW1") (pin "6") (pinfunction "6_6") (pintype "passive"))
    )
    (net (code "159") (name "unconnected-(SW2-Pad1)") (class "Default")
      (node (ref "SW2") (pin "1") (pinfunction "1_1") (pintype "passive"))
    )
    (net (code "160") (name "unconnected-(SW2-Pad2)") (class "Default")
      (node (ref "SW2") (pin "2") (pinfunction "2_2") (pintype "passive"))
    )
    (net (code "161") (name "unconnected-(SW2-Pad3)") (class "Default")
      (node (ref "SW2") (pin "3") (pinfunction "3_3") (pintype "passive"))
    )
    (net (code "162") (name "unconnected-(U$1-CH_PD-PadB2)") (class "Default")
      (node (ref "U$1") (pin "B2") (pinfunction "CH_PD_B2") (pintype "bidirectional"))
    )
    (net (code "163") (name "unconnected-(U$1-GPIO0-PadC1)") (class "Default")
      (node (ref "U$1") (pin "C1") (pinfunction "GPIO0_C1") (pintype "bidirectional"))
    )
    (net (code "164") (name "unconnected-(U$1-GPIO2-PadB1)") (class "Default")
      (node (ref "U$1") (pin "B1") (pinfunction "GPIO2_B1") (pintype "bidirectional"))
    )
    (net (code "165") (name "unconnected-(U$1-RST-PadC2)") (class "Default")
      (node (ref "U$1") (pin "C2") (pinfunction "RST_C2") (pintype "bidirectional"))
    )
    (net (code "166") (name "unconnected-(U1-NC-Pad13)") (class "Default")
      (node (ref "U1") (pin "13") (pinfunction "NC_13") (pintype "no_connect"))
    )
    (net (code "167") (name "unconnected-(U1-P0[11]{slash}RXD2{slash}SCL2{slash}MAT3[1]-Pad49)") (class "Default")
      (node (ref "U1") (pin "49") (pinfunction "P0[11]/RXD2/SCL2/MAT3[1]_49") (pintype "bidirectional"))
    )
    (net (code "168") (name "unconnected-(U1-P0[19]{slash}DSR1{slash}SDA1-Pad59)") (class "Default")
      (node (ref "U1") (pin "59") (pinfunction "P0[19]/DSR1/SDA1_59") (pintype "bidirectional"))
    )
    (net (code "169") (name "unconnected-(U1-P0[20]{slash}DTR1{slash}SCL1-Pad58)") (class "Default")
      (node (ref "U1") (pin "58") (pinfunction "P0[20]/DTR1/SCL1_58") (pintype "bidirectional"))
    )
    (net (code "170") (name "unconnected-(U1-P0[21]{slash}RI1{slash}RD1-Pad57)") (class "Default")
      (node (ref "U1") (pin "57") (pinfunction "P0[21]/RI1/RD1_57") (pintype "bidirectional"))
    )
    (net (code "171") (name "unconnected-(U1-P0[22]{slash}RTS1{slash}TD1-Pad56)") (class "Default")
      (node (ref "U1") (pin "56") (pinfunction "P0[22]/RTS1/TD1_56") (pintype "bidirectional"))
    )
    (net (code "172") (name "unconnected-(U1-P1[0]{slash}ENET_TXD0-Pad95)") (class "Default")
      (node (ref "U1") (pin "95") (pinfunction "P1[0]/ENET_TXD0_95") (pintype "bidirectional"))
    )
    (net (code "173") (name "unconnected-(U1-P1[1]{slash}ENET_TXD1-Pad94)") (class "Default")
      (node (ref "U1") (pin "94") (pinfunction "P1[1]/ENET_TXD1_94") (pintype "bidirectional"))
    )
    (net (code "174") (name "unconnected-(U1-P1[4]{slash}ENET_TX_EN-Pad93)") (class "Default")
      (node (ref "U1") (pin "93") (pinfunction "P1[4]/ENET_TX_EN_93") (pintype "bidirectional"))
    )
    (net (code "175") (name "unconnected-(U1-P1[8]{slash}ENET_CRS-Pad92)") (class "Default")
      (node (ref "U1") (pin "92") (pinfunction "P1[8]/ENET_CRS_92") (pintype "bidirectional"))
    )
    (net (code "176") (name "unconnected-(U1-P1[9]{slash}ENET_RXD0-Pad91)") (class "Default")
      (node (ref "U1") (pin "91") (pinfunction "P1[9]/ENET_RXD0_91") (pintype "bidirectional"))
    )
    (net (code "177") (name "unconnected-(U1-P1[14]{slash}ENET_RX_ER-Pad89)") (class "Default")
      (node (ref "U1") (pin "89") (pinfunction "P1[14]/ENET_RX_ER_89") (pintype "bidirectional"))
    )
    (net (code "178") (name "unconnected-(U1-P1[15]{slash}ENET_REF_CLK-Pad88)") (class "Default")
      (node (ref "U1") (pin "88") (pinfunction "P1[15]/ENET_REF_CLK_88") (pintype "bidirectional"))
    )
    (net (code "179") (name "unconnected-(U1-P1[16]{slash}ENET_MDC-Pad87)") (class "Default")
      (node (ref "U1") (pin "87") (pinfunction "P1[16]/ENET_MDC_87") (pintype "bidirectional"))
    )
    (net (code "180") (name "unconnected-(U1-P2[8]{slash}TD2{slash}TXD2-Pad65)") (class "Default")
      (node (ref "U1") (pin "65") (pinfunction "P2[8]/TD2/TXD2_65") (pintype "bidirectional"))
    )
    (net (code "181") (name "unconnected-(U1-P2[10]{slash}~{EINT0{slash}NMI}-Pad53)") (class "Default")
      (node (ref "U1") (pin "53") (pinfunction "P2[10]/~{EINT0/NMI}_53") (pintype "bidirectional"))
    )
    (net (code "182") (name "unconnected-(U1-P2[11]{slash}~{EINT1{slash}I2STX_CLK}-Pad52)") (class "Default")
      (node (ref "U1") (pin "52") (pinfunction "P2[11]/~{EINT1/I2STX_CLK}_52") (pintype "bidirectional"))
    )
    (net (code "183") (name "unconnected-(U1-P2[12]{slash}~{EINT2{slash}I2STX_WS}-Pad51)") (class "Default")
      (node (ref "U1") (pin "51") (pinfunction "P2[12]/~{EINT2/I2STX_WS}_51") (pintype "bidirectional"))
    )
    (net (code "184") (name "unconnected-(U1-P2[13]{slash}~{EINT3{slash}I2STX_SDA}-Pad50)") (class "Default")
      (node (ref "U1") (pin "50") (pinfunction "P2[13]/~{EINT3/I2STX_SDA}_50") (pintype "bidirectional"))
    )
    (net (code "185") (name "unconnected-(U1-RTCK-Pad100)") (class "Default")
      (node (ref "U1") (pin "100") (pinfunction "RTCK_100") (pintype "output"))
    )
    (net (code "186") (name "unconnected-(U1-RTCX2-Pad18)") (class "Default")
      (node (ref "U1") (pin "18") (pinfunction "RTCX2_18") (pintype "output"))
    )
    (net (code "187") (name "unconnected-(U1-TDI-Pad2)") (class "Default")
      (node (ref "U1") (pin "2") (pinfunction "TDI_2") (pintype "input"))
    )
    (net (code "188") (name "unconnected-(U1-TDO{slash}SWO-Pad1)") (class "Default")
      (node (ref "U1") (pin "1") (pinfunction "TDO/SWO_1") (pintype "output"))
    )
  )
)
